# Front_2016.net
KiCad netlist of a schematic drawn in EAGLE
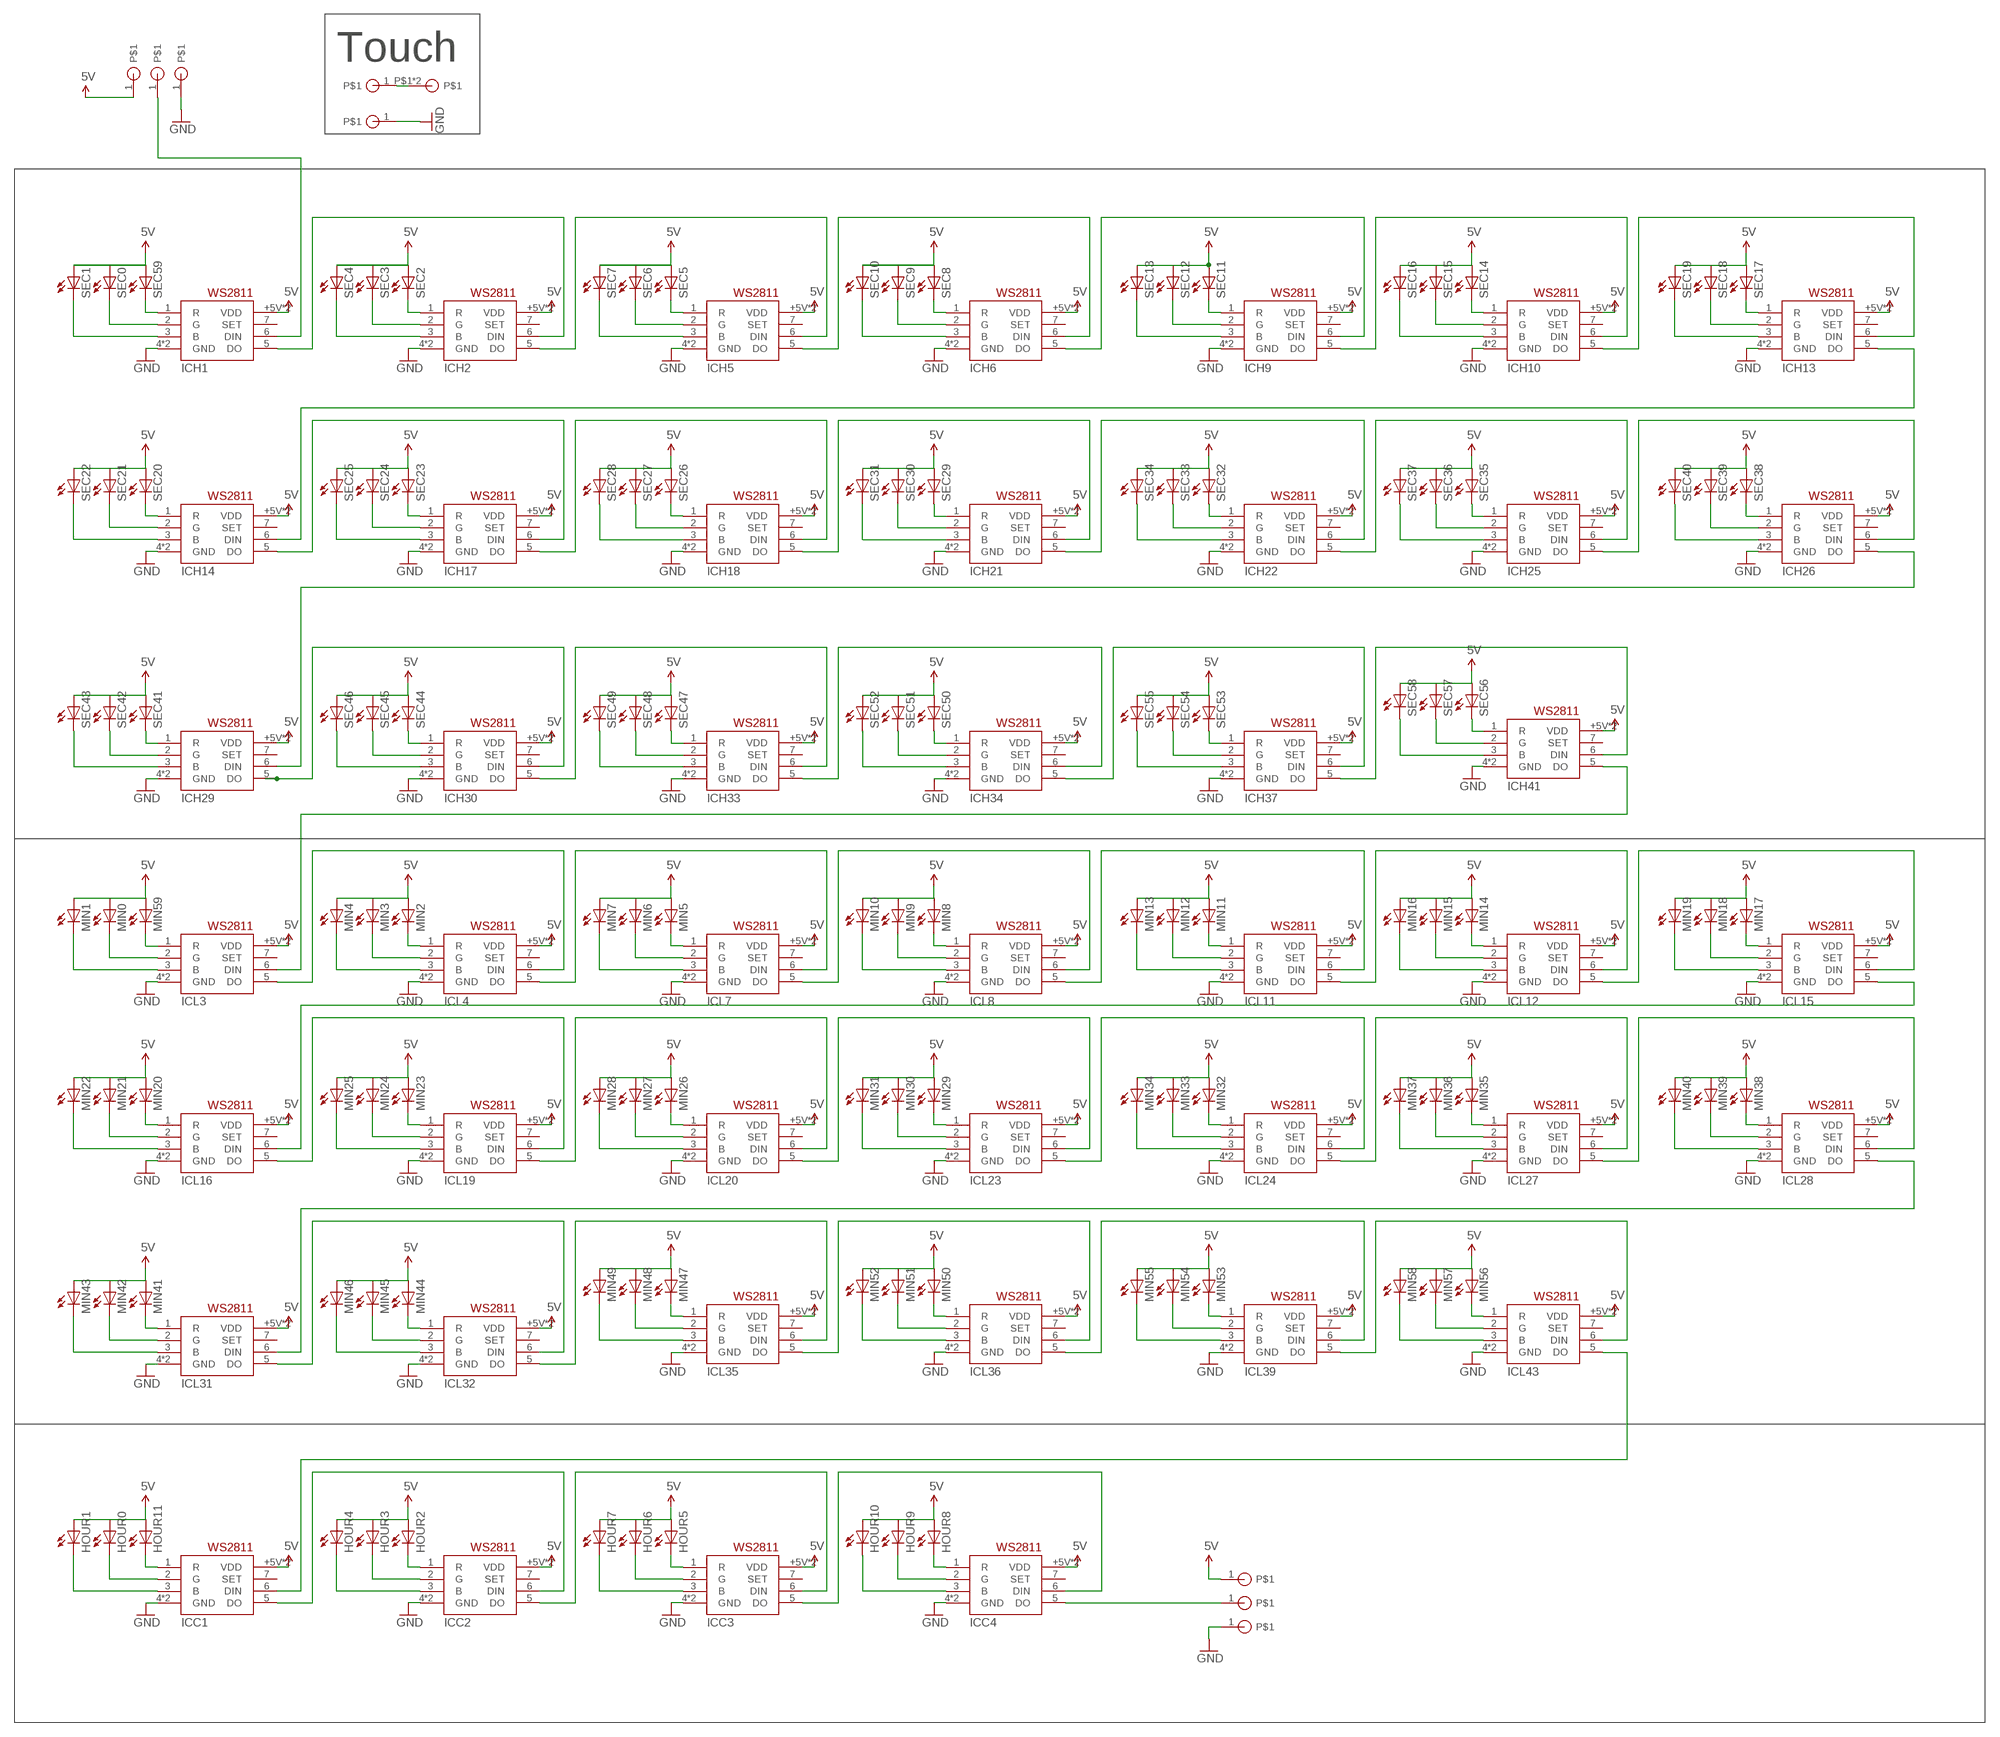
[diagram p0: schematic, sheet 1]

(export (version "E")
  (design (tool "Eeschema 10.0.6"))
  (components
    (comp (ref "+5V")
      (value "SOLDER_PAD")
      (footprint "eagle-import:SOLDER_PAD")
      (libsource (lib "eagle-import") (part "SOLDER_PAD"))
    )
    (comp (ref "+5V1")
      (value "SOLDER_PAD")
      (footprint "eagle-import:SOLDER_PAD")
      (libsource (lib "eagle-import") (part "SOLDER_PAD"))
    )
    (comp (ref "DIN")
      (value "SOLDER_PAD")
      (footprint "eagle-import:SOLDER_PAD")
      (libsource (lib "eagle-import") (part "SOLDER_PAD"))
    )
    (comp (ref "DOUT")
      (value "SOLDER_PAD")
      (footprint "eagle-import:SOLDER_PAD")
      (libsource (lib "eagle-import") (part "SOLDER_PAD"))
    )
    (comp (ref "GND")
      (value "SOLDER_PAD")
      (footprint "eagle-import:SOLDER_PAD")
      (libsource (lib "eagle-import") (part "SOLDER_PAD"))
    )
    (comp (ref "GND46")
      (value "SOLDER_PAD")
      (footprint "eagle-import:SOLDER_PAD")
      (libsource (lib "eagle-import") (part "SOLDER_PAD"))
    )
    (comp (ref "GND48")
      (value "SOLDER_PAD")
      (footprint "eagle-import:SOLDER_PAD")
      (libsource (lib "eagle-import") (part "SOLDER_PAD"))
    )
    (comp (ref "HOUR0")
      (value "LEDCHIPLED_0603")
      (footprint "eagle-import:CHIPLED_0603")
      (libsource (lib "eagle-import") (part "LEDCHIPLED_0603"))
    )
    (comp (ref "HOUR1")
      (value "LEDCHIPLED_0603")
      (footprint "eagle-import:CHIPLED_0603")
      (libsource (lib "eagle-import") (part "LEDCHIPLED_0603"))
    )
    (comp (ref "HOUR2")
      (value "LEDCHIPLED_0603")
      (footprint "eagle-import:CHIPLED_0603")
      (libsource (lib "eagle-import") (part "LEDCHIPLED_0603"))
    )
    (comp (ref "HOUR3")
      (value "LEDCHIPLED_0603")
      (footprint "eagle-import:CHIPLED_0603")
      (libsource (lib "eagle-import") (part "LEDCHIPLED_0603"))
    )
    (comp (ref "HOUR4")
      (value "LEDCHIPLED_0603")
      (footprint "eagle-import:CHIPLED_0603")
      (libsource (lib "eagle-import") (part "LEDCHIPLED_0603"))
    )
    (comp (ref "HOUR5")
      (value "LEDCHIPLED_0603")
      (footprint "eagle-import:CHIPLED_0603")
      (libsource (lib "eagle-import") (part "LEDCHIPLED_0603"))
    )
    (comp (ref "HOUR6")
      (value "LEDCHIPLED_0603")
      (footprint "eagle-import:CHIPLED_0603")
      (libsource (lib "eagle-import") (part "LEDCHIPLED_0603"))
    )
    (comp (ref "HOUR7")
      (value "LEDCHIPLED_0603")
      (footprint "eagle-import:CHIPLED_0603")
      (libsource (lib "eagle-import") (part "LEDCHIPLED_0603"))
    )
    (comp (ref "HOUR8")
      (value "LEDCHIPLED_0603")
      (footprint "eagle-import:CHIPLED_0603")
      (libsource (lib "eagle-import") (part "LEDCHIPLED_0603"))
    )
    (comp (ref "HOUR9")
      (value "LEDCHIPLED_0603")
      (footprint "eagle-import:CHIPLED_0603")
      (libsource (lib "eagle-import") (part "LEDCHIPLED_0603"))
    )
    (comp (ref "HOUR10")
      (value "LEDCHIPLED_0603")
      (footprint "eagle-import:CHIPLED_0603")
      (libsource (lib "eagle-import") (part "LEDCHIPLED_0603"))
    )
    (comp (ref "HOUR11")
      (value "LEDCHIPLED_0603")
      (footprint "eagle-import:CHIPLED_0603")
      (libsource (lib "eagle-import") (part "LEDCHIPLED_0603"))
    )
    (comp (ref "ICC1")
      (value "WS2811-SOP8")
      (footprint "eagle-import:SO08-SKINNYPADS")
      (libsource (lib "eagle-import") (part "WS2811-SOP8"))
    )
    (comp (ref "ICC2")
      (value "WS2811-SOP8")
      (footprint "eagle-import:SO08-SKINNYPADS")
      (libsource (lib "eagle-import") (part "WS2811-SOP8"))
    )
    (comp (ref "ICC3")
      (value "WS2811-SOP8")
      (footprint "eagle-import:SO08-SKINNYPADS")
      (libsource (lib "eagle-import") (part "WS2811-SOP8"))
    )
    (comp (ref "ICC4")
      (value "WS2811-SOP8")
      (footprint "eagle-import:SO08-SKINNYPADS")
      (libsource (lib "eagle-import") (part "WS2811-SOP8"))
    )
    (comp (ref "ICH1")
      (value "WS2811-SOP8")
      (footprint "eagle-import:SO08-SKINNYPADS")
      (libsource (lib "eagle-import") (part "WS2811-SOP8"))
    )
    (comp (ref "ICH2")
      (value "WS2811-SOP8")
      (footprint "eagle-import:SO08-SKINNYPADS")
      (libsource (lib "eagle-import") (part "WS2811-SOP8"))
    )
    (comp (ref "ICH5")
      (value "WS2811-SOP8")
      (footprint "eagle-import:SO08-SKINNYPADS")
      (libsource (lib "eagle-import") (part "WS2811-SOP8"))
    )
    (comp (ref "ICH6")
      (value "WS2811-SOP8")
      (footprint "eagle-import:SO08-SKINNYPADS")
      (libsource (lib "eagle-import") (part "WS2811-SOP8"))
    )
    (comp (ref "ICH9")
      (value "WS2811-SOP8")
      (footprint "eagle-import:SO08-SKINNYPADS")
      (libsource (lib "eagle-import") (part "WS2811-SOP8"))
    )
    (comp (ref "ICH10")
      (value "WS2811-SOP8")
      (footprint "eagle-import:SO08-SKINNYPADS")
      (libsource (lib "eagle-import") (part "WS2811-SOP8"))
    )
    (comp (ref "ICH13")
      (value "WS2811-SOP8")
      (footprint "eagle-import:SO08-SKINNYPADS")
      (libsource (lib "eagle-import") (part "WS2811-SOP8"))
    )
    (comp (ref "ICH14")
      (value "WS2811-SOP8")
      (footprint "eagle-import:SO08-SKINNYPADS")
      (libsource (lib "eagle-import") (part "WS2811-SOP8"))
    )
    (comp (ref "ICH17")
      (value "WS2811-SOP8")
      (footprint "eagle-import:SO08-SKINNYPADS")
      (libsource (lib "eagle-import") (part "WS2811-SOP8"))
    )
    (comp (ref "ICH18")
      (value "WS2811-SOP8")
      (footprint "eagle-import:SO08-SKINNYPADS")
      (libsource (lib "eagle-import") (part "WS2811-SOP8"))
    )
    (comp (ref "ICH21")
      (value "WS2811-SOP8")
      (footprint "eagle-import:SO08-SKINNYPADS")
      (libsource (lib "eagle-import") (part "WS2811-SOP8"))
    )
    (comp (ref "ICH22")
      (value "WS2811-SOP8")
      (footprint "eagle-import:SO08-SKINNYPADS")
      (libsource (lib "eagle-import") (part "WS2811-SOP8"))
    )
    (comp (ref "ICH25")
      (value "WS2811-SOP8")
      (footprint "eagle-import:SO08-SKINNYPADS")
      (libsource (lib "eagle-import") (part "WS2811-SOP8"))
    )
    (comp (ref "ICH26")
      (value "WS2811-SOP8")
      (footprint "eagle-import:SO08-SKINNYPADS")
      (libsource (lib "eagle-import") (part "WS2811-SOP8"))
    )
    (comp (ref "ICH29")
      (value "WS2811-SOP8")
      (footprint "eagle-import:SO08-SKINNYPADS")
      (libsource (lib "eagle-import") (part "WS2811-SOP8"))
    )
    (comp (ref "ICH30")
      (value "WS2811-SOP8")
      (footprint "eagle-import:SO08-SKINNYPADS")
      (libsource (lib "eagle-import") (part "WS2811-SOP8"))
    )
    (comp (ref "ICH33")
      (value "WS2811-SOP8")
      (footprint "eagle-import:SO08-SKINNYPADS")
      (libsource (lib "eagle-import") (part "WS2811-SOP8"))
    )
    (comp (ref "ICH34")
      (value "WS2811-SOP8")
      (footprint "eagle-import:SO08-SKINNYPADS")
      (libsource (lib "eagle-import") (part "WS2811-SOP8"))
    )
    (comp (ref "ICH37")
      (value "WS2811-SOP8")
      (footprint "eagle-import:SO08-SKINNYPADS")
      (libsource (lib "eagle-import") (part "WS2811-SOP8"))
    )
    (comp (ref "ICH41")
      (value "WS2811-SOP8")
      (footprint "eagle-import:SO08-SKINNYPADS")
      (libsource (lib "eagle-import") (part "WS2811-SOP8"))
    )
    (comp (ref "ICL3")
      (value "WS2811-SOP8")
      (footprint "eagle-import:SO08-SKINNYPADS")
      (libsource (lib "eagle-import") (part "WS2811-SOP8"))
    )
    (comp (ref "ICL4")
      (value "WS2811-SOP8")
      (footprint "eagle-import:SO08-SKINNYPADS")
      (libsource (lib "eagle-import") (part "WS2811-SOP8"))
    )
    (comp (ref "ICL7")
      (value "WS2811-SOP8")
      (footprint "eagle-import:SO08-SKINNYPADS")
      (libsource (lib "eagle-import") (part "WS2811-SOP8"))
    )
    (comp (ref "ICL8")
      (value "WS2811-SOP8")
      (footprint "eagle-import:SO08-SKINNYPADS")
      (libsource (lib "eagle-import") (part "WS2811-SOP8"))
    )
    (comp (ref "ICL11")
      (value "WS2811-SOP8")
      (footprint "eagle-import:SO08-SKINNYPADS")
      (libsource (lib "eagle-import") (part "WS2811-SOP8"))
    )
    (comp (ref "ICL12")
      (value "WS2811-SOP8")
      (footprint "eagle-import:SO08-SKINNYPADS")
      (libsource (lib "eagle-import") (part "WS2811-SOP8"))
    )
    (comp (ref "ICL15")
      (value "WS2811-SOP8")
      (footprint "eagle-import:SO08-SKINNYPADS")
      (libsource (lib "eagle-import") (part "WS2811-SOP8"))
    )
    (comp (ref "ICL16")
      (value "WS2811-SOP8")
      (footprint "eagle-import:SO08-SKINNYPADS")
      (libsource (lib "eagle-import") (part "WS2811-SOP8"))
    )
    (comp (ref "ICL19")
      (value "WS2811-SOP8")
      (footprint "eagle-import:SO08-SKINNYPADS")
      (libsource (lib "eagle-import") (part "WS2811-SOP8"))
    )
    (comp (ref "ICL20")
      (value "WS2811-SOP8")
      (footprint "eagle-import:SO08-SKINNYPADS")
      (libsource (lib "eagle-import") (part "WS2811-SOP8"))
    )
    (comp (ref "ICL23")
      (value "WS2811-SOP8")
      (footprint "eagle-import:SO08-SKINNYPADS")
      (libsource (lib "eagle-import") (part "WS2811-SOP8"))
    )
    (comp (ref "ICL24")
      (value "WS2811-SOP8")
      (footprint "eagle-import:SO08-SKINNYPADS")
      (libsource (lib "eagle-import") (part "WS2811-SOP8"))
    )
    (comp (ref "ICL27")
      (value "WS2811-SOP8")
      (footprint "eagle-import:SO08-SKINNYPADS")
      (libsource (lib "eagle-import") (part "WS2811-SOP8"))
    )
    (comp (ref "ICL28")
      (value "WS2811-SOP8")
      (footprint "eagle-import:SO08-SKINNYPADS")
      (libsource (lib "eagle-import") (part "WS2811-SOP8"))
    )
    (comp (ref "ICL31")
      (value "WS2811-SOP8")
      (footprint "eagle-import:SO08-SKINNYPADS")
      (libsource (lib "eagle-import") (part "WS2811-SOP8"))
    )
    (comp (ref "ICL32")
      (value "WS2811-SOP8")
      (footprint "eagle-import:SO08-SKINNYPADS")
      (libsource (lib "eagle-import") (part "WS2811-SOP8"))
    )
    (comp (ref "ICL35")
      (value "WS2811-SOP8")
      (footprint "eagle-import:SO08-SKINNYPADS")
      (libsource (lib "eagle-import") (part "WS2811-SOP8"))
    )
    (comp (ref "ICL36")
      (value "WS2811-SOP8")
      (footprint "eagle-import:SO08-SKINNYPADS")
      (libsource (lib "eagle-import") (part "WS2811-SOP8"))
    )
    (comp (ref "ICL39")
      (value "WS2811-SOP8")
      (footprint "eagle-import:SO08-SKINNYPADS")
      (libsource (lib "eagle-import") (part "WS2811-SOP8"))
    )
    (comp (ref "ICL43")
      (value "WS2811-SOP8")
      (footprint "eagle-import:SO08-SKINNYPADS")
      (libsource (lib "eagle-import") (part "WS2811-SOP8"))
    )
    (comp (ref "MIN0")
      (value "LEDCHIPLED_0603")
      (footprint "eagle-import:CHIPLED_0603")
      (libsource (lib "eagle-import") (part "LEDCHIPLED_0603"))
    )
    (comp (ref "MIN1")
      (value "LEDCHIPLED_0603")
      (footprint "eagle-import:CHIPLED_0603")
      (libsource (lib "eagle-import") (part "LEDCHIPLED_0603"))
    )
    (comp (ref "MIN2")
      (value "LEDCHIPLED_0603")
      (footprint "eagle-import:CHIPLED_0603")
      (libsource (lib "eagle-import") (part "LEDCHIPLED_0603"))
    )
    (comp (ref "MIN3")
      (value "LEDCHIPLED_0603")
      (footprint "eagle-import:CHIPLED_0603")
      (libsource (lib "eagle-import") (part "LEDCHIPLED_0603"))
    )
    (comp (ref "MIN4")
      (value "LEDCHIPLED_0603")
      (footprint "eagle-import:CHIPLED_0603")
      (libsource (lib "eagle-import") (part "LEDCHIPLED_0603"))
    )
    (comp (ref "MIN5")
      (value "LEDCHIPLED_0603")
      (footprint "eagle-import:CHIPLED_0603")
      (libsource (lib "eagle-import") (part "LEDCHIPLED_0603"))
    )
    (comp (ref "MIN6")
      (value "LEDCHIPLED_0603")
      (footprint "eagle-import:CHIPLED_0603")
      (libsource (lib "eagle-import") (part "LEDCHIPLED_0603"))
    )
    (comp (ref "MIN7")
      (value "LEDCHIPLED_0603")
      (footprint "eagle-import:CHIPLED_0603")
      (libsource (lib "eagle-import") (part "LEDCHIPLED_0603"))
    )
    (comp (ref "MIN8")
      (value "LEDCHIPLED_0603")
      (footprint "eagle-import:CHIPLED_0603")
      (libsource (lib "eagle-import") (part "LEDCHIPLED_0603"))
    )
    (comp (ref "MIN9")
      (value "LEDCHIPLED_0603")
      (footprint "eagle-import:CHIPLED_0603")
      (libsource (lib "eagle-import") (part "LEDCHIPLED_0603"))
    )
    (comp (ref "MIN10")
      (value "LEDCHIPLED_0603")
      (footprint "eagle-import:CHIPLED_0603")
      (libsource (lib "eagle-import") (part "LEDCHIPLED_0603"))
    )
    (comp (ref "MIN11")
      (value "LEDCHIPLED_0603")
      (footprint "eagle-import:CHIPLED_0603")
      (libsource (lib "eagle-import") (part "LEDCHIPLED_0603"))
    )
    (comp (ref "MIN12")
      (value "LEDCHIPLED_0603")
      (footprint "eagle-import:CHIPLED_0603")
      (libsource (lib "eagle-import") (part "LEDCHIPLED_0603"))
    )
    (comp (ref "MIN13")
      (value "LEDCHIPLED_0603")
      (footprint "eagle-import:CHIPLED_0603")
      (libsource (lib "eagle-import") (part "LEDCHIPLED_0603"))
    )
    (comp (ref "MIN14")
      (value "LEDCHIPLED_0603")
      (footprint "eagle-import:CHIPLED_0603")
      (libsource (lib "eagle-import") (part "LEDCHIPLED_0603"))
    )
    (comp (ref "MIN15")
      (value "LEDCHIPLED_0603")
      (footprint "eagle-import:CHIPLED_0603")
      (libsource (lib "eagle-import") (part "LEDCHIPLED_0603"))
    )
    (comp (ref "MIN16")
      (value "LEDCHIPLED_0603")
      (footprint "eagle-import:CHIPLED_0603")
      (libsource (lib "eagle-import") (part "LEDCHIPLED_0603"))
    )
    (comp (ref "MIN17")
      (value "LEDCHIPLED_0603")
      (footprint "eagle-import:CHIPLED_0603")
      (libsource (lib "eagle-import") (part "LEDCHIPLED_0603"))
    )
    (comp (ref "MIN18")
      (value "LEDCHIPLED_0603")
      (footprint "eagle-import:CHIPLED_0603")
      (libsource (lib "eagle-import") (part "LEDCHIPLED_0603"))
    )
    (comp (ref "MIN19")
      (value "LEDCHIPLED_0603")
      (footprint "eagle-import:CHIPLED_0603")
      (libsource (lib "eagle-import") (part "LEDCHIPLED_0603"))
    )
    (comp (ref "MIN20")
      (value "LEDCHIPLED_0603")
      (footprint "eagle-import:CHIPLED_0603")
      (libsource (lib "eagle-import") (part "LEDCHIPLED_0603"))
    )
    (comp (ref "MIN21")
      (value "LEDCHIPLED_0603")
      (footprint "eagle-import:CHIPLED_0603")
      (libsource (lib "eagle-import") (part "LEDCHIPLED_0603"))
    )
    (comp (ref "MIN22")
      (value "LEDCHIPLED_0603")
      (footprint "eagle-import:CHIPLED_0603")
      (libsource (lib "eagle-import") (part "LEDCHIPLED_0603"))
    )
    (comp (ref "MIN23")
      (value "LEDCHIPLED_0603")
      (footprint "eagle-import:CHIPLED_0603")
      (libsource (lib "eagle-import") (part "LEDCHIPLED_0603"))
    )
    (comp (ref "MIN24")
      (value "LEDCHIPLED_0603")
      (footprint "eagle-import:CHIPLED_0603")
      (libsource (lib "eagle-import") (part "LEDCHIPLED_0603"))
    )
    (comp (ref "MIN25")
      (value "LEDCHIPLED_0603")
      (footprint "eagle-import:CHIPLED_0603")
      (libsource (lib "eagle-import") (part "LEDCHIPLED_0603"))
    )
    (comp (ref "MIN26")
      (value "LEDCHIPLED_0603")
      (footprint "eagle-import:CHIPLED_0603")
      (libsource (lib "eagle-import") (part "LEDCHIPLED_0603"))
    )
    (comp (ref "MIN27")
      (value "LEDCHIPLED_0603")
      (footprint "eagle-import:CHIPLED_0603")
      (libsource (lib "eagle-import") (part "LEDCHIPLED_0603"))
    )
    (comp (ref "MIN28")
      (value "LEDCHIPLED_0603")
      (footprint "eagle-import:CHIPLED_0603")
      (libsource (lib "eagle-import") (part "LEDCHIPLED_0603"))
    )
    (comp (ref "MIN29")
      (value "LEDCHIPLED_0603")
      (footprint "eagle-import:CHIPLED_0603")
      (libsource (lib "eagle-import") (part "LEDCHIPLED_0603"))
    )
    (comp (ref "MIN30")
      (value "LEDCHIPLED_0603")
      (footprint "eagle-import:CHIPLED_0603")
      (libsource (lib "eagle-import") (part "LEDCHIPLED_0603"))
    )
    (comp (ref "MIN31")
      (value "LEDCHIPLED_0603")
      (footprint "eagle-import:CHIPLED_0603")
      (libsource (lib "eagle-import") (part "LEDCHIPLED_0603"))
    )
    (comp (ref "MIN32")
      (value "LEDCHIPLED_0603")
      (footprint "eagle-import:CHIPLED_0603")
      (libsource (lib "eagle-import") (part "LEDCHIPLED_0603"))
    )
    (comp (ref "MIN33")
      (value "LEDCHIPLED_0603")
      (footprint "eagle-import:CHIPLED_0603")
      (libsource (lib "eagle-import") (part "LEDCHIPLED_0603"))
    )
    (comp (ref "MIN34")
      (value "LEDCHIPLED_0603")
      (footprint "eagle-import:CHIPLED_0603")
      (libsource (lib "eagle-import") (part "LEDCHIPLED_0603"))
    )
    (comp (ref "MIN35")
      (value "LEDCHIPLED_0603")
      (footprint "eagle-import:CHIPLED_0603")
      (libsource (lib "eagle-import") (part "LEDCHIPLED_0603"))
    )
    (comp (ref "MIN36")
      (value "LEDCHIPLED_0603")
      (footprint "eagle-import:CHIPLED_0603")
      (libsource (lib "eagle-import") (part "LEDCHIPLED_0603"))
    )
    (comp (ref "MIN37")
      (value "LEDCHIPLED_0603")
      (footprint "eagle-import:CHIPLED_0603")
      (libsource (lib "eagle-import") (part "LEDCHIPLED_0603"))
    )
    (comp (ref "MIN38")
      (value "LEDCHIPLED_0603")
      (footprint "eagle-import:CHIPLED_0603")
      (libsource (lib "eagle-import") (part "LEDCHIPLED_0603"))
    )
    (comp (ref "MIN39")
      (value "LEDCHIPLED_0603")
      (footprint "eagle-import:CHIPLED_0603")
      (libsource (lib "eagle-import") (part "LEDCHIPLED_0603"))
    )
    (comp (ref "MIN40")
      (value "LEDCHIPLED_0603")
      (footprint "eagle-import:CHIPLED_0603")
      (libsource (lib "eagle-import") (part "LEDCHIPLED_0603"))
    )
    (comp (ref "MIN41")
      (value "LEDCHIPLED_0603")
      (footprint "eagle-import:CHIPLED_0603")
      (libsource (lib "eagle-import") (part "LEDCHIPLED_0603"))
    )
    (comp (ref "MIN42")
      (value "LEDCHIPLED_0603")
      (footprint "eagle-import:CHIPLED_0603")
      (libsource (lib "eagle-import") (part "LEDCHIPLED_0603"))
    )
    (comp (ref "MIN43")
      (value "LEDCHIPLED_0603")
      (footprint "eagle-import:CHIPLED_0603")
      (libsource (lib "eagle-import") (part "LEDCHIPLED_0603"))
    )
    (comp (ref "MIN44")
      (value "LEDCHIPLED_0603")
      (footprint "eagle-import:CHIPLED_0603")
      (libsource (lib "eagle-import") (part "LEDCHIPLED_0603"))
    )
    (comp (ref "MIN45")
      (value "LEDCHIPLED_0603")
      (footprint "eagle-import:CHIPLED_0603")
      (libsource (lib "eagle-import") (part "LEDCHIPLED_0603"))
    )
    (comp (ref "MIN46")
      (value "LEDCHIPLED_0603")
      (footprint "eagle-import:CHIPLED_0603")
      (libsource (lib "eagle-import") (part "LEDCHIPLED_0603"))
    )
    (comp (ref "MIN47")
      (value "LEDCHIPLED_0603")
      (footprint "eagle-import:CHIPLED_0603")
      (libsource (lib "eagle-import") (part "LEDCHIPLED_0603"))
    )
    (comp (ref "MIN48")
      (value "LEDCHIPLED_0603")
      (footprint "eagle-import:CHIPLED_0603")
      (libsource (lib "eagle-import") (part "LEDCHIPLED_0603"))
    )
    (comp (ref "MIN49")
      (value "LEDCHIPLED_0603")
      (footprint "eagle-import:CHIPLED_0603")
      (libsource (lib "eagle-import") (part "LEDCHIPLED_0603"))
    )
    (comp (ref "MIN50")
      (value "LEDCHIPLED_0603")
      (footprint "eagle-import:CHIPLED_0603")
      (libsource (lib "eagle-import") (part "LEDCHIPLED_0603"))
    )
    (comp (ref "MIN51")
      (value "LEDCHIPLED_0603")
      (footprint "eagle-import:CHIPLED_0603")
      (libsource (lib "eagle-import") (part "LEDCHIPLED_0603"))
    )
    (comp (ref "MIN52")
      (value "LEDCHIPLED_0603")
      (footprint "eagle-import:CHIPLED_0603")
      (libsource (lib "eagle-import") (part "LEDCHIPLED_0603"))
    )
    (comp (ref "MIN53")
      (value "LEDCHIPLED_0603")
      (footprint "eagle-import:CHIPLED_0603")
      (libsource (lib "eagle-import") (part "LEDCHIPLED_0603"))
    )
    (comp (ref "MIN54")
      (value "LEDCHIPLED_0603")
      (footprint "eagle-import:CHIPLED_0603")
      (libsource (lib "eagle-import") (part "LEDCHIPLED_0603"))
    )
    (comp (ref "MIN55")
      (value "LEDCHIPLED_0603")
      (footprint "eagle-import:CHIPLED_0603")
      (libsource (lib "eagle-import") (part "LEDCHIPLED_0603"))
    )
    (comp (ref "MIN56")
      (value "LEDCHIPLED_0603")
      (footprint "eagle-import:CHIPLED_0603")
      (libsource (lib "eagle-import") (part "LEDCHIPLED_0603"))
    )
    (comp (ref "MIN57")
      (value "LEDCHIPLED_0603")
      (footprint "eagle-import:CHIPLED_0603")
      (libsource (lib "eagle-import") (part "LEDCHIPLED_0603"))
    )
    (comp (ref "MIN58")
      (value "LEDCHIPLED_0603")
      (footprint "eagle-import:CHIPLED_0603")
      (libsource (lib "eagle-import") (part "LEDCHIPLED_0603"))
    )
    (comp (ref "MIN59")
      (value "LEDCHIPLED_0603")
      (footprint "eagle-import:CHIPLED_0603")
      (libsource (lib "eagle-import") (part "LEDCHIPLED_0603"))
    )
    (comp (ref "SEC0")
      (value "LEDCHIPLED_0603")
      (footprint "eagle-import:CHIPLED_0603")
      (libsource (lib "eagle-import") (part "LEDCHIPLED_0603"))
    )
    (comp (ref "SEC1")
      (value "LEDCHIPLED_0603")
      (footprint "eagle-import:CHIPLED_0603")
      (libsource (lib "eagle-import") (part "LEDCHIPLED_0603"))
    )
    (comp (ref "SEC2")
      (value "LEDCHIPLED_0603")
      (footprint "eagle-import:CHIPLED_0603")
      (libsource (lib "eagle-import") (part "LEDCHIPLED_0603"))
    )
    (comp (ref "SEC3")
      (value "LEDCHIPLED_0603")
      (footprint "eagle-import:CHIPLED_0603")
      (libsource (lib "eagle-import") (part "LEDCHIPLED_0603"))
    )
    (comp (ref "SEC4")
      (value "LEDCHIPLED_0603")
      (footprint "eagle-import:CHIPLED_0603")
      (libsource (lib "eagle-import") (part "LEDCHIPLED_0603"))
    )
    (comp (ref "SEC5")
      (value "LEDCHIPLED_0603")
      (footprint "eagle-import:CHIPLED_0603")
      (libsource (lib "eagle-import") (part "LEDCHIPLED_0603"))
    )
    (comp (ref "SEC6")
      (value "LEDCHIPLED_0603")
      (footprint "eagle-import:CHIPLED_0603")
      (libsource (lib "eagle-import") (part "LEDCHIPLED_0603"))
    )
    (comp (ref "SEC7")
      (value "LEDCHIPLED_0603")
      (footprint "eagle-import:CHIPLED_0603")
      (libsource (lib "eagle-import") (part "LEDCHIPLED_0603"))
    )
    (comp (ref "SEC8")
      (value "LEDCHIPLED_0603")
      (footprint "eagle-import:CHIPLED_0603")
      (libsource (lib "eagle-import") (part "LEDCHIPLED_0603"))
    )
    (comp (ref "SEC9")
      (value "LEDCHIPLED_0603")
      (footprint "eagle-import:CHIPLED_0603")
      (libsource (lib "eagle-import") (part "LEDCHIPLED_0603"))
    )
    (comp (ref "SEC10")
      (value "LEDCHIPLED_0603")
      (footprint "eagle-import:CHIPLED_0603")
      (libsource (lib "eagle-import") (part "LEDCHIPLED_0603"))
    )
    (comp (ref "SEC11")
      (value "LEDCHIPLED_0603")
      (footprint "eagle-import:CHIPLED_0603")
      (libsource (lib "eagle-import") (part "LEDCHIPLED_0603"))
    )
    (comp (ref "SEC12")
      (value "LEDCHIPLED_0603")
      (footprint "eagle-import:CHIPLED_0603")
      (libsource (lib "eagle-import") (part "LEDCHIPLED_0603"))
    )
    (comp (ref "SEC13")
      (value "LEDCHIPLED_0603")
      (footprint "eagle-import:CHIPLED_0603")
      (libsource (lib "eagle-import") (part "LEDCHIPLED_0603"))
    )
    (comp (ref "SEC14")
      (value "LEDCHIPLED_0603")
      (footprint "eagle-import:CHIPLED_0603")
      (libsource (lib "eagle-import") (part "LEDCHIPLED_0603"))
    )
    (comp (ref "SEC15")
      (value "LEDCHIPLED_0603")
      (footprint "eagle-import:CHIPLED_0603")
      (libsource (lib "eagle-import") (part "LEDCHIPLED_0603"))
    )
    (comp (ref "SEC16")
      (value "LEDCHIPLED_0603")
      (footprint "eagle-import:CHIPLED_0603")
      (libsource (lib "eagle-import") (part "LEDCHIPLED_0603"))
    )
    (comp (ref "SEC17")
      (value "LEDCHIPLED_0603")
      (footprint "eagle-import:CHIPLED_0603")
      (libsource (lib "eagle-import") (part "LEDCHIPLED_0603"))
    )
    (comp (ref "SEC18")
      (value "LEDCHIPLED_0603")
      (footprint "eagle-import:CHIPLED_0603")
      (libsource (lib "eagle-import") (part "LEDCHIPLED_0603"))
    )
    (comp (ref "SEC19")
      (value "LEDCHIPLED_0603")
      (footprint "eagle-import:CHIPLED_0603")
      (libsource (lib "eagle-import") (part "LEDCHIPLED_0603"))
    )
    (comp (ref "SEC20")
      (value "LEDCHIPLED_0603")
      (footprint "eagle-import:CHIPLED_0603")
      (libsource (lib "eagle-import") (part "LEDCHIPLED_0603"))
    )
    (comp (ref "SEC21")
      (value "LEDCHIPLED_0603")
      (footprint "eagle-import:CHIPLED_0603")
      (libsource (lib "eagle-import") (part "LEDCHIPLED_0603"))
    )
    (comp (ref "SEC22")
      (value "LEDCHIPLED_0603")
      (footprint "eagle-import:CHIPLED_0603")
      (libsource (lib "eagle-import") (part "LEDCHIPLED_0603"))
    )
    (comp (ref "SEC23")
      (value "LEDCHIPLED_0603")
      (footprint "eagle-import:CHIPLED_0603")
      (libsource (lib "eagle-import") (part "LEDCHIPLED_0603"))
    )
    (comp (ref "SEC24")
      (value "LEDCHIPLED_0603")
      (footprint "eagle-import:CHIPLED_0603")
      (libsource (lib "eagle-import") (part "LEDCHIPLED_0603"))
    )
    (comp (ref "SEC25")
      (value "LEDCHIPLED_0603")
      (footprint "eagle-import:CHIPLED_0603")
      (libsource (lib "eagle-import") (part "LEDCHIPLED_0603"))
    )
    (comp (ref "SEC26")
      (value "LEDCHIPLED_0603")
      (footprint "eagle-import:CHIPLED_0603")
      (libsource (lib "eagle-import") (part "LEDCHIPLED_0603"))
    )
    (comp (ref "SEC27")
      (value "LEDCHIPLED_0603")
      (footprint "eagle-import:CHIPLED_0603")
      (libsource (lib "eagle-import") (part "LEDCHIPLED_0603"))
    )
    (comp (ref "SEC28")
      (value "LEDCHIPLED_0603")
      (footprint "eagle-import:CHIPLED_0603")
      (libsource (lib "eagle-import") (part "LEDCHIPLED_0603"))
    )
    (comp (ref "SEC29")
      (value "LEDCHIPLED_0603")
      (footprint "eagle-import:CHIPLED_0603")
      (libsource (lib "eagle-import") (part "LEDCHIPLED_0603"))
    )
    (comp (ref "SEC30")
      (value "LEDCHIPLED_0603")
      (footprint "eagle-import:CHIPLED_0603")
      (libsource (lib "eagle-import") (part "LEDCHIPLED_0603"))
    )
    (comp (ref "SEC31")
      (value "LEDCHIPLED_0603")
      (footprint "eagle-import:CHIPLED_0603")
      (libsource (lib "eagle-import") (part "LEDCHIPLED_0603"))
    )
    (comp (ref "SEC32")
      (value "LEDCHIPLED_0603")
      (footprint "eagle-import:CHIPLED_0603")
      (libsource (lib "eagle-import") (part "LEDCHIPLED_0603"))
    )
    (comp (ref "SEC33")
      (value "LEDCHIPLED_0603")
      (footprint "eagle-import:CHIPLED_0603")
      (libsource (lib "eagle-import") (part "LEDCHIPLED_0603"))
    )
    (comp (ref "SEC34")
      (value "LEDCHIPLED_0603")
      (footprint "eagle-import:CHIPLED_0603")
      (libsource (lib "eagle-import") (part "LEDCHIPLED_0603"))
    )
    (comp (ref "SEC35")
      (value "LEDCHIPLED_0603")
      (footprint "eagle-import:CHIPLED_0603")
      (libsource (lib "eagle-import") (part "LEDCHIPLED_0603"))
    )
    (comp (ref "SEC36")
      (value "LEDCHIPLED_0603")
      (footprint "eagle-import:CHIPLED_0603")
      (libsource (lib "eagle-import") (part "LEDCHIPLED_0603"))
    )
    (comp (ref "SEC37")
      (value "LEDCHIPLED_0603")
      (footprint "eagle-import:CHIPLED_0603")
      (libsource (lib "eagle-import") (part "LEDCHIPLED_0603"))
    )
    (comp (ref "SEC38")
      (value "LEDCHIPLED_0603")
      (footprint "eagle-import:CHIPLED_0603")
      (libsource (lib "eagle-import") (part "LEDCHIPLED_0603"))
    )
    (comp (ref "SEC39")
      (value "LEDCHIPLED_0603")
      (footprint "eagle-import:CHIPLED_0603")
      (libsource (lib "eagle-import") (part "LEDCHIPLED_0603"))
    )
    (comp (ref "SEC40")
      (value "LEDCHIPLED_0603")
      (footprint "eagle-import:CHIPLED_0603")
      (libsource (lib "eagle-import") (part "LEDCHIPLED_0603"))
    )
    (comp (ref "SEC41")
      (value "LEDCHIPLED_0603")
      (footprint "eagle-import:CHIPLED_0603")
      (libsource (lib "eagle-import") (part "LEDCHIPLED_0603"))
    )
    (comp (ref "SEC42")
      (value "LEDCHIPLED_0603")
      (footprint "eagle-import:CHIPLED_0603")
      (libsource (lib "eagle-import") (part "LEDCHIPLED_0603"))
    )
    (comp (ref "SEC43")
      (value "LEDCHIPLED_0603")
      (footprint "eagle-import:CHIPLED_0603")
      (libsource (lib "eagle-import") (part "LEDCHIPLED_0603"))
    )
    (comp (ref "SEC44")
      (value "LEDCHIPLED_0603")
      (footprint "eagle-import:CHIPLED_0603")
      (libsource (lib "eagle-import") (part "LEDCHIPLED_0603"))
    )
    (comp (ref "SEC45")
      (value "LEDCHIPLED_0603")
      (footprint "eagle-import:CHIPLED_0603")
      (libsource (lib "eagle-import") (part "LEDCHIPLED_0603"))
    )
    (comp (ref "SEC46")
      (value "LEDCHIPLED_0603")
      (footprint "eagle-import:CHIPLED_0603")
      (libsource (lib "eagle-import") (part "LEDCHIPLED_0603"))
    )
    (comp (ref "SEC47")
      (value "LEDCHIPLED_0603")
      (footprint "eagle-import:CHIPLED_0603")
      (libsource (lib "eagle-import") (part "LEDCHIPLED_0603"))
    )
    (comp (ref "SEC48")
      (value "LEDCHIPLED_0603")
      (footprint "eagle-import:CHIPLED_0603")
      (libsource (lib "eagle-import") (part "LEDCHIPLED_0603"))
    )
    (comp (ref "SEC49")
      (value "LEDCHIPLED_0603")
      (footprint "eagle-import:CHIPLED_0603")
      (libsource (lib "eagle-import") (part "LEDCHIPLED_0603"))
    )
    (comp (ref "SEC50")
      (value "LEDCHIPLED_0603")
      (footprint "eagle-import:CHIPLED_0603")
      (libsource (lib "eagle-import") (part "LEDCHIPLED_0603"))
    )
    (comp (ref "SEC51")
      (value "LEDCHIPLED_0603")
      (footprint "eagle-import:CHIPLED_0603")
      (libsource (lib "eagle-import") (part "LEDCHIPLED_0603"))
    )
    (comp (ref "SEC52")
      (value "LEDCHIPLED_0603")
      (footprint "eagle-import:CHIPLED_0603")
      (libsource (lib "eagle-import") (part "LEDCHIPLED_0603"))
    )
    (comp (ref "SEC53")
      (value "LEDCHIPLED_0603")
      (footprint "eagle-import:CHIPLED_0603")
      (libsource (lib "eagle-import") (part "LEDCHIPLED_0603"))
    )
    (comp (ref "SEC54")
      (value "LEDCHIPLED_0603")
      (footprint "eagle-import:CHIPLED_0603")
      (libsource (lib "eagle-import") (part "LEDCHIPLED_0603"))
    )
    (comp (ref "SEC55")
      (value "LEDCHIPLED_0603")
      (footprint "eagle-import:CHIPLED_0603")
      (libsource (lib "eagle-import") (part "LEDCHIPLED_0603"))
    )
    (comp (ref "SEC56")
      (value "LEDCHIPLED_0603")
      (footprint "eagle-import:CHIPLED_0603")
      (libsource (lib "eagle-import") (part "LEDCHIPLED_0603"))
    )
    (comp (ref "SEC57")
      (value "LEDCHIPLED_0603")
      (footprint "eagle-import:CHIPLED_0603")
      (libsource (lib "eagle-import") (part "LEDCHIPLED_0603"))
    )
    (comp (ref "SEC58")
      (value "LEDCHIPLED_0603")
      (footprint "eagle-import:CHIPLED_0603")
      (libsource (lib "eagle-import") (part "LEDCHIPLED_0603"))
    )
    (comp (ref "SEC59")
      (value "LEDCHIPLED_0603")
      (footprint "eagle-import:CHIPLED_0603")
      (libsource (lib "eagle-import") (part "LEDCHIPLED_0603"))
    )
    (comp (ref "TOUCH")
      (value "SOLDER_PAD")
      (footprint "eagle-import:SOLDER_PAD")
      (libsource (lib "eagle-import") (part "SOLDER_PAD"))
    )
    (comp (ref "U$2")
      (value "TOUCH_PAD_LARGE")
      (footprint "eagle-import:TOUCH_PAD_LARGE")
      (libsource (lib "eagle-import") (part "TOUCH_PAD_LARGE"))
    )
  )
  (nets
    (net (code "1") (name "5V") (class "Default")
      (node (ref "+5V") (pin "1") (pinfunction "P$1_1") (pintype "bidirectional"))
      (node (ref "+5V1") (pin "1") (pinfunction "P$1_1") (pintype "bidirectional"))
      (node (ref "HOUR0") (pin "A") (pinfunction "A_A") (pintype "passive"))
      (node (ref "HOUR1") (pin "A") (pinfunction "A_A") (pintype "passive"))
      (node (ref "HOUR10") (pin "A") (pinfunction "A_A") (pintype "passive"))
      (node (ref "HOUR11") (pin "A") (pinfunction "A_A") (pintype "passive"))
      (node (ref "HOUR2") (pin "A") (pinfunction "A_A") (pintype "passive"))
      (node (ref "HOUR3") (pin "A") (pinfunction "A_A") (pintype "passive"))
      (node (ref "HOUR4") (pin "A") (pinfunction "A_A") (pintype "passive"))
      (node (ref "HOUR5") (pin "A") (pinfunction "A_A") (pintype "passive"))
      (node (ref "HOUR6") (pin "A") (pinfunction "A_A") (pintype "passive"))
      (node (ref "HOUR7") (pin "A") (pinfunction "A_A") (pintype "passive"))
      (node (ref "HOUR8") (pin "A") (pinfunction "A_A") (pintype "passive"))
      (node (ref "HOUR9") (pin "A") (pinfunction "A_A") (pintype "passive"))
      (node (ref "ICC1") (pin "+5V") (pinfunction "VDD_+5V") (pintype "power_in"))
      (node (ref "ICC1") (pin "8") (pinfunction "VDD_8") (pintype "power_in"))
      (node (ref "ICC2") (pin "+5V") (pinfunction "VDD_+5V") (pintype "power_in"))
      (node (ref "ICC2") (pin "8") (pinfunction "VDD_8") (pintype "power_in"))
      (node (ref "ICC3") (pin "+5V") (pinfunction "VDD_+5V") (pintype "power_in"))
      (node (ref "ICC3") (pin "8") (pinfunction "VDD_8") (pintype "power_in"))
      (node (ref "ICC4") (pin "+5V") (pinfunction "VDD_+5V") (pintype "power_in"))
      (node (ref "ICC4") (pin "8") (pinfunction "VDD_8") (pintype "power_in"))
      (node (ref "ICH1") (pin "+5V") (pinfunction "VDD_+5V") (pintype "power_in"))
      (node (ref "ICH1") (pin "8") (pinfunction "VDD_8") (pintype "power_in"))
      (node (ref "ICH10") (pin "+5V") (pinfunction "VDD_+5V") (pintype "power_in"))
      (node (ref "ICH10") (pin "8") (pinfunction "VDD_8") (pintype "power_in"))
      (node (ref "ICH13") (pin "+5V") (pinfunction "VDD_+5V") (pintype "power_in"))
      (node (ref "ICH13") (pin "8") (pinfunction "VDD_8") (pintype "power_in"))
      (node (ref "ICH14") (pin "+5V") (pinfunction "VDD_+5V") (pintype "power_in"))
      (node (ref "ICH14") (pin "8") (pinfunction "VDD_8") (pintype "power_in"))
      (node (ref "ICH17") (pin "+5V") (pinfunction "VDD_+5V") (pintype "power_in"))
      (node (ref "ICH17") (pin "8") (pinfunction "VDD_8") (pintype "power_in"))
      (node (ref "ICH18") (pin "+5V") (pinfunction "VDD_+5V") (pintype "power_in"))
      (node (ref "ICH18") (pin "8") (pinfunction "VDD_8") (pintype "power_in"))
      (node (ref "ICH2") (pin "+5V") (pinfunction "VDD_+5V") (pintype "power_in"))
      (node (ref "ICH2") (pin "8") (pinfunction "VDD_8") (pintype "power_in"))
      (node (ref "ICH21") (pin "+5V") (pinfunction "VDD_+5V") (pintype "power_in"))
      (node (ref "ICH21") (pin "8") (pinfunction "VDD_8") (pintype "power_in"))
      (node (ref "ICH22") (pin "+5V") (pinfunction "VDD_+5V") (pintype "power_in"))
      (node (ref "ICH22") (pin "8") (pinfunction "VDD_8") (pintype "power_in"))
      (node (ref "ICH25") (pin "+5V") (pinfunction "VDD_+5V") (pintype "power_in"))
      (node (ref "ICH25") (pin "8") (pinfunction "VDD_8") (pintype "power_in"))
      (node (ref "ICH26") (pin "+5V") (pinfunction "VDD_+5V") (pintype "power_in"))
      (node (ref "ICH26") (pin "8") (pinfunction "VDD_8") (pintype "power_in"))
      (node (ref "ICH29") (pin "+5V") (pinfunction "VDD_+5V") (pintype "power_in"))
      (node (ref "ICH29") (pin "8") (pinfunction "VDD_8") (pintype "power_in"))
      (node (ref "ICH30") (pin "+5V") (pinfunction "VDD_+5V") (pintype "power_in"))
      (node (ref "ICH30") (pin "8") (pinfunction "VDD_8") (pintype "power_in"))
      (node (ref "ICH33") (pin "+5V") (pinfunction "VDD_+5V") (pintype "power_in"))
      (node (ref "ICH33") (pin "8") (pinfunction "VDD_8") (pintype "power_in"))
      (node (ref "ICH34") (pin "+5V") (pinfunction "VDD_+5V") (pintype "power_in"))
      (node (ref "ICH34") (pin "8") (pinfunction "VDD_8") (pintype "power_in"))
      (node (ref "ICH37") (pin "+5V") (pinfunction "VDD_+5V") (pintype "power_in"))
      (node (ref "ICH37") (pin "8") (pinfunction "VDD_8") (pintype "power_in"))
      (node (ref "ICH41") (pin "+5V") (pinfunction "VDD_+5V") (pintype "power_in"))
      (node (ref "ICH41") (pin "8") (pinfunction "VDD_8") (pintype "power_in"))
      (node (ref "ICH5") (pin "+5V") (pinfunction "VDD_+5V") (pintype "power_in"))
      (node (ref "ICH5") (pin "8") (pinfunction "VDD_8") (pintype "power_in"))
      (node (ref "ICH6") (pin "+5V") (pinfunction "VDD_+5V") (pintype "power_in"))
      (node (ref "ICH6") (pin "8") (pinfunction "VDD_8") (pintype "power_in"))
      (node (ref "ICH9") (pin "+5V") (pinfunction "VDD_+5V") (pintype "power_in"))
      (node (ref "ICH9") (pin "8") (pinfunction "VDD_8") (pintype "power_in"))
      (node (ref "ICL11") (pin "+5V") (pinfunction "VDD_+5V") (pintype "power_in"))
      (node (ref "ICL11") (pin "8") (pinfunction "VDD_8") (pintype "power_in"))
      (node (ref "ICL12") (pin "+5V") (pinfunction "VDD_+5V") (pintype "power_in"))
      (node (ref "ICL12") (pin "8") (pinfunction "VDD_8") (pintype "power_in"))
      (node (ref "ICL15") (pin "+5V") (pinfunction "VDD_+5V") (pintype "power_in"))
      (node (ref "ICL15") (pin "8") (pinfunction "VDD_8") (pintype "power_in"))
      (node (ref "ICL16") (pin "+5V") (pinfunction "VDD_+5V") (pintype "power_in"))
      (node (ref "ICL16") (pin "8") (pinfunction "VDD_8") (pintype "power_in"))
      (node (ref "ICL19") (pin "+5V") (pinfunction "VDD_+5V") (pintype "power_in"))
      (node (ref "ICL19") (pin "8") (pinfunction "VDD_8") (pintype "power_in"))
      (node (ref "ICL20") (pin "+5V") (pinfunction "VDD_+5V") (pintype "power_in"))
      (node (ref "ICL20") (pin "8") (pinfunction "VDD_8") (pintype "power_in"))
      (node (ref "ICL23") (pin "+5V") (pinfunction "VDD_+5V") (pintype "power_in"))
      (node (ref "ICL23") (pin "8") (pinfunction "VDD_8") (pintype "power_in"))
      (node (ref "ICL24") (pin "+5V") (pinfunction "VDD_+5V") (pintype "power_in"))
      (node (ref "ICL24") (pin "8") (pinfunction "VDD_8") (pintype "power_in"))
      (node (ref "ICL27") (pin "+5V") (pinfunction "VDD_+5V") (pintype "power_in"))
      (node (ref "ICL27") (pin "8") (pinfunction "VDD_8") (pintype "power_in"))
      (node (ref "ICL28") (pin "+5V") (pinfunction "VDD_+5V") (pintype "power_in"))
      (node (ref "ICL28") (pin "8") (pinfunction "VDD_8") (pintype "power_in"))
      (node (ref "ICL3") (pin "+5V") (pinfunction "VDD_+5V") (pintype "power_in"))
      (node (ref "ICL3") (pin "8") (pinfunction "VDD_8") (pintype "power_in"))
      (node (ref "ICL31") (pin "+5V") (pinfunction "VDD_+5V") (pintype "power_in"))
      (node (ref "ICL31") (pin "8") (pinfunction "VDD_8") (pintype "power_in"))
      (node (ref "ICL32") (pin "+5V") (pinfunction "VDD_+5V") (pintype "power_in"))
      (node (ref "ICL32") (pin "8") (pinfunction "VDD_8") (pintype "power_in"))
      (node (ref "ICL35") (pin "+5V") (pinfunction "VDD_+5V") (pintype "power_in"))
      (node (ref "ICL35") (pin "8") (pinfunction "VDD_8") (pintype "power_in"))
      (node (ref "ICL36") (pin "+5V") (pinfunction "VDD_+5V") (pintype "power_in"))
      (node (ref "ICL36") (pin "8") (pinfunction "VDD_8") (pintype "power_in"))
      (node (ref "ICL39") (pin "+5V") (pinfunction "VDD_+5V") (pintype "power_in"))
      (node (ref "ICL39") (pin "8") (pinfunction "VDD_8") (pintype "power_in"))
      (node (ref "ICL4") (pin "+5V") (pinfunction "VDD_+5V") (pintype "power_in"))
      (node (ref "ICL4") (pin "8") (pinfunction "VDD_8") (pintype "power_in"))
      (node (ref "ICL43") (pin "+5V") (pinfunction "VDD_+5V") (pintype "power_in"))
      (node (ref "ICL43") (pin "8") (pinfunction "VDD_8") (pintype "power_in"))
      (node (ref "ICL7") (pin "+5V") (pinfunction "VDD_+5V") (pintype "power_in"))
      (node (ref "ICL7") (pin "8") (pinfunction "VDD_8") (pintype "power_in"))
      (node (ref "ICL8") (pin "+5V") (pinfunction "VDD_+5V") (pintype "power_in"))
      (node (ref "ICL8") (pin "8") (pinfunction "VDD_8") (pintype "power_in"))
      (node (ref "MIN0") (pin "A") (pinfunction "A_A") (pintype "passive"))
      (node (ref "MIN1") (pin "A") (pinfunction "A_A") (pintype "passive"))
      (node (ref "MIN10") (pin "A") (pinfunction "A_A") (pintype "passive"))
      (node (ref "MIN11") (pin "A") (pinfunction "A_A") (pintype "passive"))
      (node (ref "MIN12") (pin "A") (pinfunction "A_A") (pintype "passive"))
      (node (ref "MIN13") (pin "A") (pinfunction "A_A") (pintype "passive"))
      (node (ref "MIN14") (pin "A") (pinfunction "A_A") (pintype "passive"))
      (node (ref "MIN15") (pin "A") (pinfunction "A_A") (pintype "passive"))
      (node (ref "MIN16") (pin "A") (pinfunction "A_A") (pintype "passive"))
      (node (ref "MIN17") (pin "A") (pinfunction "A_A") (pintype "passive"))
      (node (ref "MIN18") (pin "A") (pinfunction "A_A") (pintype "passive"))
      (node (ref "MIN19") (pin "A") (pinfunction "A_A") (pintype "passive"))
      (node (ref "MIN2") (pin "A") (pinfunction "A_A") (pintype "passive"))
      (node (ref "MIN20") (pin "A") (pinfunction "A_A") (pintype "passive"))
      (node (ref "MIN21") (pin "A") (pinfunction "A_A") (pintype "passive"))
      (node (ref "MIN22") (pin "A") (pinfunction "A_A") (pintype "passive"))
      (node (ref "MIN23") (pin "A") (pinfunction "A_A") (pintype "passive"))
      (node (ref "MIN24") (pin "A") (pinfunction "A_A") (pintype "passive"))
      (node (ref "MIN25") (pin "A") (pinfunction "A_A") (pintype "passive"))
      (node (ref "MIN26") (pin "A") (pinfunction "A_A") (pintype "passive"))
      (node (ref "MIN27") (pin "A") (pinfunction "A_A") (pintype "passive"))
      (node (ref "MIN28") (pin "A") (pinfunction "A_A") (pintype "passive"))
      (node (ref "MIN29") (pin "A") (pinfunction "A_A") (pintype "passive"))
      (node (ref "MIN3") (pin "A") (pinfunction "A_A") (pintype "passive"))
      (node (ref "MIN30") (pin "A") (pinfunction "A_A") (pintype "passive"))
      (node (ref "MIN31") (pin "A") (pinfunction "A_A") (pintype "passive"))
      (node (ref "MIN32") (pin "A") (pinfunction "A_A") (pintype "passive"))
      (node (ref "MIN33") (pin "A") (pinfunction "A_A") (pintype "passive"))
      (node (ref "MIN34") (pin "A") (pinfunction "A_A") (pintype "passive"))
      (node (ref "MIN35") (pin "A") (pinfunction "A_A") (pintype "passive"))
      (node (ref "MIN36") (pin "A") (pinfunction "A_A") (pintype "passive"))
      (node (ref "MIN37") (pin "A") (pinfunction "A_A") (pintype "passive"))
      (node (ref "MIN38") (pin "A") (pinfunction "A_A") (pintype "passive"))
      (node (ref "MIN39") (pin "A") (pinfunction "A_A") (pintype "passive"))
      (node (ref "MIN4") (pin "A") (pinfunction "A_A") (pintype "passive"))
      (node (ref "MIN40") (pin "A") (pinfunction "A_A") (pintype "passive"))
      (node (ref "MIN41") (pin "A") (pinfunction "A_A") (pintype "passive"))
      (node (ref "MIN42") (pin "A") (pinfunction "A_A") (pintype "passive"))
      (node (ref "MIN43") (pin "A") (pinfunction "A_A") (pintype "passive"))
      (node (ref "MIN44") (pin "A") (pinfunction "A_A") (pintype "passive"))
      (node (ref "MIN45") (pin "A") (pinfunction "A_A") (pintype "passive"))
      (node (ref "MIN46") (pin "A") (pinfunction "A_A") (pintype "passive"))
      (node (ref "MIN47") (pin "A") (pinfunction "A_A") (pintype "passive"))
      (node (ref "MIN48") (pin "A") (pinfunction "A_A") (pintype "passive"))
      (node (ref "MIN49") (pin "A") (pinfunction "A_A") (pintype "passive"))
      (node (ref "MIN5") (pin "A") (pinfunction "A_A") (pintype "passive"))
      (node (ref "MIN50") (pin "A") (pinfunction "A_A") (pintype "passive"))
      (node (ref "MIN51") (pin "A") (pinfunction "A_A") (pintype "passive"))
      (node (ref "MIN52") (pin "A") (pinfunction "A_A") (pintype "passive"))
      (node (ref "MIN53") (pin "A") (pinfunction "A_A") (pintype "passive"))
      (node (ref "MIN54") (pin "A") (pinfunction "A_A") (pintype "passive"))
      (node (ref "MIN55") (pin "A") (pinfunction "A_A") (pintype "passive"))
      (node (ref "MIN56") (pin "A") (pinfunction "A_A") (pintype "passive"))
      (node (ref "MIN57") (pin "A") (pinfunction "A_A") (pintype "passive"))
      (node (ref "MIN58") (pin "A") (pinfunction "A_A") (pintype "passive"))
      (node (ref "MIN59") (pin "A") (pinfunction "A_A") (pintype "passive"))
      (node (ref "MIN6") (pin "A") (pinfunction "A_A") (pintype "passive"))
      (node (ref "MIN7") (pin "A") (pinfunction "A_A") (pintype "passive"))
      (node (ref "MIN8") (pin "A") (pinfunction "A_A") (pintype "passive"))
      (node (ref "MIN9") (pin "A") (pinfunction "A_A") (pintype "passive"))
      (node (ref "SEC0") (pin "A") (pinfunction "A_A") (pintype "passive"))
      (node (ref "SEC1") (pin "A") (pinfunction "A_A") (pintype "passive"))
      (node (ref "SEC10") (pin "A") (pinfunction "A_A") (pintype "passive"))
      (node (ref "SEC11") (pin "A") (pinfunction "A_A") (pintype "passive"))
      (node (ref "SEC12") (pin "A") (pinfunction "A_A") (pintype "passive"))
      (node (ref "SEC13") (pin "A") (pinfunction "A_A") (pintype "passive"))
      (node (ref "SEC14") (pin "A") (pinfunction "A_A") (pintype "passive"))
      (node (ref "SEC15") (pin "A") (pinfunction "A_A") (pintype "passive"))
      (node (ref "SEC16") (pin "A") (pinfunction "A_A") (pintype "passive"))
      (node (ref "SEC17") (pin "A") (pinfunction "A_A") (pintype "passive"))
      (node (ref "SEC18") (pin "A") (pinfunction "A_A") (pintype "passive"))
      (node (ref "SEC19") (pin "A") (pinfunction "A_A") (pintype "passive"))
      (node (ref "SEC2") (pin "A") (pinfunction "A_A") (pintype "passive"))
      (node (ref "SEC20") (pin "A") (pinfunction "A_A") (pintype "passive"))
      (node (ref "SEC21") (pin "A") (pinfunction "A_A") (pintype "passive"))
      (node (ref "SEC22") (pin "A") (pinfunction "A_A") (pintype "passive"))
      (node (ref "SEC23") (pin "A") (pinfunction "A_A") (pintype "passive"))
      (node (ref "SEC24") (pin "A") (pinfunction "A_A") (pintype "passive"))
      (node (ref "SEC25") (pin "A") (pinfunction "A_A") (pintype "passive"))
      (node (ref "SEC26") (pin "A") (pinfunction "A_A") (pintype "passive"))
      (node (ref "SEC27") (pin "A") (pinfunction "A_A") (pintype "passive"))
      (node (ref "SEC28") (pin "A") (pinfunction "A_A") (pintype "passive"))
      (node (ref "SEC29") (pin "A") (pinfunction "A_A") (pintype "passive"))
      (node (ref "SEC3") (pin "A") (pinfunction "A_A") (pintype "passive"))
      (node (ref "SEC30") (pin "A") (pinfunction "A_A") (pintype "passive"))
      (node (ref "SEC31") (pin "A") (pinfunction "A_A") (pintype "passive"))
      (node (ref "SEC32") (pin "A") (pinfunction "A_A") (pintype "passive"))
      (node (ref "SEC33") (pin "A") (pinfunction "A_A") (pintype "passive"))
      (node (ref "SEC34") (pin "A") (pinfunction "A_A") (pintype "passive"))
      (node (ref "SEC35") (pin "A") (pinfunction "A_A") (pintype "passive"))
      (node (ref "SEC36") (pin "A") (pinfunction "A_A") (pintype "passive"))
      (node (ref "SEC37") (pin "A") (pinfunction "A_A") (pintype "passive"))
      (node (ref "SEC38") (pin "A") (pinfunction "A_A") (pintype "passive"))
      (node (ref "SEC39") (pin "A") (pinfunction "A_A") (pintype "passive"))
      (node (ref "SEC4") (pin "A") (pinfunction "A_A") (pintype "passive"))
      (node (ref "SEC40") (pin "A") (pinfunction "A_A") (pintype "passive"))
      (node (ref "SEC41") (pin "A") (pinfunction "A_A") (pintype "passive"))
      (node (ref "SEC42") (pin "A") (pinfunction "A_A") (pintype "passive"))
      (node (ref "SEC43") (pin "A") (pinfunction "A_A") (pintype "passive"))
      (node (ref "SEC44") (pin "A") (pinfunction "A_A") (pintype "passive"))
      (node (ref "SEC45") (pin "A") (pinfunction "A_A") (pintype "passive"))
      (node (ref "SEC46") (pin "A") (pinfunction "A_A") (pintype "passive"))
      (node (ref "SEC47") (pin "A") (pinfunction "A_A") (pintype "passive"))
      (node (ref "SEC48") (pin "A") (pinfunction "A_A") (pintype "passive"))
      (node (ref "SEC49") (pin "A") (pinfunction "A_A") (pintype "passive"))
      (node (ref "SEC5") (pin "A") (pinfunction "A_A") (pintype "passive"))
      (node (ref "SEC50") (pin "A") (pinfunction "A_A") (pintype "passive"))
      (node (ref "SEC51") (pin "A") (pinfunction "A_A") (pintype "passive"))
      (node (ref "SEC52") (pin "A") (pinfunction "A_A") (pintype "passive"))
      (node (ref "SEC53") (pin "A") (pinfunction "A_A") (pintype "passive"))
      (node (ref "SEC54") (pin "A") (pinfunction "A_A") (pintype "passive"))
      (node (ref "SEC55") (pin "A") (pinfunction "A_A") (pintype "passive"))
      (node (ref "SEC56") (pin "A") (pinfunction "A_A") (pintype "passive"))
      (node (ref "SEC57") (pin "A") (pinfunction "A_A") (pintype "passive"))
      (node (ref "SEC58") (pin "A") (pinfunction "A_A") (pintype "passive"))
      (node (ref "SEC59") (pin "A") (pinfunction "A_A") (pintype "passive"))
      (node (ref "SEC6") (pin "A") (pinfunction "A_A") (pintype "passive"))
      (node (ref "SEC7") (pin "A") (pinfunction "A_A") (pintype "passive"))
      (node (ref "SEC8") (pin "A") (pinfunction "A_A") (pintype "passive"))
      (node (ref "SEC9") (pin "A") (pinfunction "A_A") (pintype "passive"))
    )
    (net (code "2") (name "GND") (class "Default")
      (node (ref "GND") (pin "1") (pinfunction "P$1_1") (pintype "bidirectional"))
      (node (ref "GND46") (pin "1") (pinfunction "P$1_1") (pintype "bidirectional"))
      (node (ref "GND48") (pin "1") (pinfunction "P$1_1") (pintype "bidirectional"))
      (node (ref "ICC1") (pin "4") (pinfunction "GND_4") (pintype "power_in"))
      (node (ref "ICC1") (pin "GND") (pinfunction "GND_GND") (pintype "power_in"))
      (node (ref "ICC2") (pin "4") (pinfunction "GND_4") (pintype "power_in"))
      (node (ref "ICC2") (pin "GND") (pinfunction "GND_GND") (pintype "power_in"))
      (node (ref "ICC3") (pin "4") (pinfunction "GND_4") (pintype "power_in"))
      (node (ref "ICC3") (pin "GND") (pinfunction "GND_GND") (pintype "power_in"))
      (node (ref "ICC4") (pin "4") (pinfunction "GND_4") (pintype "power_in"))
      (node (ref "ICC4") (pin "GND") (pinfunction "GND_GND") (pintype "power_in"))
      (node (ref "ICH1") (pin "4") (pinfunction "GND_4") (pintype "power_in"))
      (node (ref "ICH1") (pin "GND") (pinfunction "GND_GND") (pintype "power_in"))
      (node (ref "ICH10") (pin "4") (pinfunction "GND_4") (pintype "power_in"))
      (node (ref "ICH10") (pin "GND") (pinfunction "GND_GND") (pintype "power_in"))
      (node (ref "ICH13") (pin "4") (pinfunction "GND_4") (pintype "power_in"))
      (node (ref "ICH13") (pin "GND") (pinfunction "GND_GND") (pintype "power_in"))
      (node (ref "ICH14") (pin "4") (pinfunction "GND_4") (pintype "power_in"))
      (node (ref "ICH14") (pin "GND") (pinfunction "GND_GND") (pintype "power_in"))
      (node (ref "ICH17") (pin "4") (pinfunction "GND_4") (pintype "power_in"))
      (node (ref "ICH17") (pin "GND") (pinfunction "GND_GND") (pintype "power_in"))
      (node (ref "ICH18") (pin "4") (pinfunction "GND_4") (pintype "power_in"))
      (node (ref "ICH18") (pin "GND") (pinfunction "GND_GND") (pintype "power_in"))
      (node (ref "ICH2") (pin "4") (pinfunction "GND_4") (pintype "power_in"))
      (node (ref "ICH2") (pin "GND") (pinfunction "GND_GND") (pintype "power_in"))
      (node (ref "ICH21") (pin "4") (pinfunction "GND_4") (pintype "power_in"))
      (node (ref "ICH21") (pin "GND") (pinfunction "GND_GND") (pintype "power_in"))
      (node (ref "ICH22") (pin "4") (pinfunction "GND_4") (pintype "power_in"))
      (node (ref "ICH22") (pin "GND") (pinfunction "GND_GND") (pintype "power_in"))
      (node (ref "ICH25") (pin "4") (pinfunction "GND_4") (pintype "power_in"))
      (node (ref "ICH25") (pin "GND") (pinfunction "GND_GND") (pintype "power_in"))
      (node (ref "ICH26") (pin "4") (pinfunction "GND_4") (pintype "power_in"))
      (node (ref "ICH26") (pin "GND") (pinfunction "GND_GND") (pintype "power_in"))
      (node (ref "ICH29") (pin "4") (pinfunction "GND_4") (pintype "power_in"))
      (node (ref "ICH29") (pin "GND") (pinfunction "GND_GND") (pintype "power_in"))
      (node (ref "ICH30") (pin "4") (pinfunction "GND_4") (pintype "power_in"))
      (node (ref "ICH30") (pin "GND") (pinfunction "GND_GND") (pintype "power_in"))
      (node (ref "ICH33") (pin "4") (pinfunction "GND_4") (pintype "power_in"))
      (node (ref "ICH33") (pin "GND") (pinfunction "GND_GND") (pintype "power_in"))
      (node (ref "ICH34") (pin "4") (pinfunction "GND_4") (pintype "power_in"))
      (node (ref "ICH34") (pin "GND") (pinfunction "GND_GND") (pintype "power_in"))
      (node (ref "ICH37") (pin "4") (pinfunction "GND_4") (pintype "power_in"))
      (node (ref "ICH37") (pin "GND") (pinfunction "GND_GND") (pintype "power_in"))
      (node (ref "ICH41") (pin "4") (pinfunction "GND_4") (pintype "power_in"))
      (node (ref "ICH41") (pin "GND") (pinfunction "GND_GND") (pintype "power_in"))
      (node (ref "ICH5") (pin "4") (pinfunction "GND_4") (pintype "power_in"))
      (node (ref "ICH5") (pin "GND") (pinfunction "GND_GND") (pintype "power_in"))
      (node (ref "ICH6") (pin "4") (pinfunction "GND_4") (pintype "power_in"))
      (node (ref "ICH6") (pin "GND") (pinfunction "GND_GND") (pintype "power_in"))
      (node (ref "ICH9") (pin "4") (pinfunction "GND_4") (pintype "power_in"))
      (node (ref "ICH9") (pin "GND") (pinfunction "GND_GND") (pintype "power_in"))
      (node (ref "ICL11") (pin "4") (pinfunction "GND_4") (pintype "power_in"))
      (node (ref "ICL11") (pin "GND") (pinfunction "GND_GND") (pintype "power_in"))
      (node (ref "ICL12") (pin "4") (pinfunction "GND_4") (pintype "power_in"))
      (node (ref "ICL12") (pin "GND") (pinfunction "GND_GND") (pintype "power_in"))
      (node (ref "ICL15") (pin "4") (pinfunction "GND_4") (pintype "power_in"))
      (node (ref "ICL15") (pin "GND") (pinfunction "GND_GND") (pintype "power_in"))
      (node (ref "ICL16") (pin "4") (pinfunction "GND_4") (pintype "power_in"))
      (node (ref "ICL16") (pin "GND") (pinfunction "GND_GND") (pintype "power_in"))
      (node (ref "ICL19") (pin "4") (pinfunction "GND_4") (pintype "power_in"))
      (node (ref "ICL19") (pin "GND") (pinfunction "GND_GND") (pintype "power_in"))
      (node (ref "ICL20") (pin "4") (pinfunction "GND_4") (pintype "power_in"))
      (node (ref "ICL20") (pin "GND") (pinfunction "GND_GND") (pintype "power_in"))
      (node (ref "ICL23") (pin "4") (pinfunction "GND_4") (pintype "power_in"))
      (node (ref "ICL23") (pin "GND") (pinfunction "GND_GND") (pintype "power_in"))
      (node (ref "ICL24") (pin "4") (pinfunction "GND_4") (pintype "power_in"))
      (node (ref "ICL24") (pin "GND") (pinfunction "GND_GND") (pintype "power_in"))
      (node (ref "ICL27") (pin "4") (pinfunction "GND_4") (pintype "power_in"))
      (node (ref "ICL27") (pin "GND") (pinfunction "GND_GND") (pintype "power_in"))
      (node (ref "ICL28") (pin "4") (pinfunction "GND_4") (pintype "power_in"))
      (node (ref "ICL28") (pin "GND") (pinfunction "GND_GND") (pintype "power_in"))
      (node (ref "ICL3") (pin "4") (pinfunction "GND_4") (pintype "power_in"))
      (node (ref "ICL3") (pin "GND") (pinfunction "GND_GND") (pintype "power_in"))
      (node (ref "ICL31") (pin "4") (pinfunction "GND_4") (pintype "power_in"))
      (node (ref "ICL31") (pin "GND") (pinfunction "GND_GND") (pintype "power_in"))
      (node (ref "ICL32") (pin "4") (pinfunction "GND_4") (pintype "power_in"))
      (node (ref "ICL32") (pin "GND") (pinfunction "GND_GND") (pintype "power_in"))
      (node (ref "ICL35") (pin "4") (pinfunction "GND_4") (pintype "power_in"))
      (node (ref "ICL35") (pin "GND") (pinfunction "GND_GND") (pintype "power_in"))
      (node (ref "ICL36") (pin "4") (pinfunction "GND_4") (pintype "power_in"))
      (node (ref "ICL36") (pin "GND") (pinfunction "GND_GND") (pintype "power_in"))
      (node (ref "ICL39") (pin "4") (pinfunction "GND_4") (pintype "power_in"))
      (node (ref "ICL39") (pin "GND") (pinfunction "GND_GND") (pintype "power_in"))
      (node (ref "ICL4") (pin "4") (pinfunction "GND_4") (pintype "power_in"))
      (node (ref "ICL4") (pin "GND") (pinfunction "GND_GND") (pintype "power_in"))
      (node (ref "ICL43") (pin "4") (pinfunction "GND_4") (pintype "power_in"))
      (node (ref "ICL43") (pin "GND") (pinfunction "GND_GND") (pintype "power_in"))
      (node (ref "ICL7") (pin "4") (pinfunction "GND_4") (pintype "power_in"))
      (node (ref "ICL7") (pin "GND") (pinfunction "GND_GND") (pintype "power_in"))
      (node (ref "ICL8") (pin "4") (pinfunction "GND_4") (pintype "power_in"))
      (node (ref "ICL8") (pin "GND") (pinfunction "GND_GND") (pintype "power_in"))
    )
    (net (code "3") (name "Net-(DIN-P$1)") (class "Default")
      (node (ref "DIN") (pin "1") (pinfunction "P$1_1") (pintype "bidirectional"))
      (node (ref "ICH1") (pin "6") (pinfunction "DIN_6") (pintype "input"))
    )
    (net (code "4") (name "Net-(DOUT-P$1)") (class "Default")
      (node (ref "DOUT") (pin "1") (pinfunction "P$1_1") (pintype "bidirectional"))
      (node (ref "ICC4") (pin "5") (pinfunction "DO_5") (pintype "output"))
    )
    (net (code "5") (name "Net-(ICC1-B)") (class "Default")
      (node (ref "HOUR1") (pin "C") (pinfunction "C_C") (pintype "passive"))
      (node (ref "ICC1") (pin "3") (pinfunction "B_3") (pintype "open_collector"))
    )
    (net (code "6") (name "Net-(ICC1-DIN)") (class "Default")
      (node (ref "ICC1") (pin "6") (pinfunction "DIN_6") (pintype "input"))
      (node (ref "ICL43") (pin "5") (pinfunction "DO_5") (pintype "output"))
    )
    (net (code "7") (name "Net-(ICC1-DO)") (class "Default")
      (node (ref "ICC1") (pin "5") (pinfunction "DO_5") (pintype "output"))
      (node (ref "ICC2") (pin "6") (pinfunction "DIN_6") (pintype "input"))
    )
    (net (code "8") (name "Net-(ICC1-G)") (class "Default")
      (node (ref "HOUR0") (pin "C") (pinfunction "C_C") (pintype "passive"))
      (node (ref "ICC1") (pin "2") (pinfunction "G_2") (pintype "open_collector"))
    )
    (net (code "9") (name "Net-(ICC1-R)") (class "Default")
      (node (ref "HOUR11") (pin "C") (pinfunction "C_C") (pintype "passive"))
      (node (ref "ICC1") (pin "1") (pinfunction "R_1") (pintype "open_collector"))
    )
    (net (code "10") (name "Net-(ICC2-B)") (class "Default")
      (node (ref "HOUR4") (pin "C") (pinfunction "C_C") (pintype "passive"))
      (node (ref "ICC2") (pin "3") (pinfunction "B_3") (pintype "open_collector"))
    )
    (net (code "11") (name "Net-(ICC2-DO)") (class "Default")
      (node (ref "ICC2") (pin "5") (pinfunction "DO_5") (pintype "output"))
      (node (ref "ICC3") (pin "6") (pinfunction "DIN_6") (pintype "input"))
    )
    (net (code "12") (name "Net-(ICC2-G)") (class "Default")
      (node (ref "HOUR3") (pin "C") (pinfunction "C_C") (pintype "passive"))
      (node (ref "ICC2") (pin "2") (pinfunction "G_2") (pintype "open_collector"))
    )
    (net (code "13") (name "Net-(ICC2-R)") (class "Default")
      (node (ref "HOUR2") (pin "C") (pinfunction "C_C") (pintype "passive"))
      (node (ref "ICC2") (pin "1") (pinfunction "R_1") (pintype "open_collector"))
    )
    (net (code "14") (name "Net-(ICC3-B)") (class "Default")
      (node (ref "HOUR7") (pin "C") (pinfunction "C_C") (pintype "passive"))
      (node (ref "ICC3") (pin "3") (pinfunction "B_3") (pintype "open_collector"))
    )
    (net (code "15") (name "Net-(ICC3-DO)") (class "Default")
      (node (ref "ICC3") (pin "5") (pinfunction "DO_5") (pintype "output"))
      (node (ref "ICC4") (pin "6") (pinfunction "DIN_6") (pintype "input"))
    )
    (net (code "16") (name "Net-(ICC3-G)") (class "Default")
      (node (ref "HOUR6") (pin "C") (pinfunction "C_C") (pintype "passive"))
      (node (ref "ICC3") (pin "2") (pinfunction "G_2") (pintype "open_collector"))
    )
    (net (code "17") (name "Net-(ICC3-R)") (class "Default")
      (node (ref "HOUR5") (pin "C") (pinfunction "C_C") (pintype "passive"))
      (node (ref "ICC3") (pin "1") (pinfunction "R_1") (pintype "open_collector"))
    )
    (net (code "18") (name "Net-(ICC4-B)") (class "Default")
      (node (ref "HOUR10") (pin "C") (pinfunction "C_C") (pintype "passive"))
      (node (ref "ICC4") (pin "3") (pinfunction "B_3") (pintype "open_collector"))
    )
    (net (code "19") (name "Net-(ICC4-G)") (class "Default")
      (node (ref "HOUR9") (pin "C") (pinfunction "C_C") (pintype "passive"))
      (node (ref "ICC4") (pin "2") (pinfunction "G_2") (pintype "open_collector"))
    )
    (net (code "20") (name "Net-(ICC4-R)") (class "Default")
      (node (ref "HOUR8") (pin "C") (pinfunction "C_C") (pintype "passive"))
      (node (ref "ICC4") (pin "1") (pinfunction "R_1") (pintype "open_collector"))
    )
    (net (code "21") (name "Net-(ICH1-B)") (class "Default")
      (node (ref "ICH1") (pin "3") (pinfunction "B_3") (pintype "open_collector"))
      (node (ref "SEC1") (pin "C") (pinfunction "C_C") (pintype "passive"))
    )
    (net (code "22") (name "Net-(ICH1-DO)") (class "Default")
      (node (ref "ICH1") (pin "5") (pinfunction "DO_5") (pintype "output"))
      (node (ref "ICH2") (pin "6") (pinfunction "DIN_6") (pintype "input"))
    )
    (net (code "23") (name "Net-(ICH1-G)") (class "Default")
      (node (ref "ICH1") (pin "2") (pinfunction "G_2") (pintype "open_collector"))
      (node (ref "SEC0") (pin "C") (pinfunction "C_C") (pintype "passive"))
    )
    (net (code "24") (name "Net-(ICH1-R)") (class "Default")
      (node (ref "ICH1") (pin "1") (pinfunction "R_1") (pintype "open_collector"))
      (node (ref "SEC59") (pin "C") (pinfunction "C_C") (pintype "passive"))
    )
    (net (code "25") (name "Net-(ICH2-B)") (class "Default")
      (node (ref "ICH2") (pin "3") (pinfunction "B_3") (pintype "open_collector"))
      (node (ref "SEC4") (pin "C") (pinfunction "C_C") (pintype "passive"))
    )
    (net (code "26") (name "Net-(ICH2-DO)") (class "Default")
      (node (ref "ICH2") (pin "5") (pinfunction "DO_5") (pintype "output"))
      (node (ref "ICH5") (pin "6") (pinfunction "DIN_6") (pintype "input"))
    )
    (net (code "27") (name "Net-(ICH2-G)") (class "Default")
      (node (ref "ICH2") (pin "2") (pinfunction "G_2") (pintype "open_collector"))
      (node (ref "SEC3") (pin "C") (pinfunction "C_C") (pintype "passive"))
    )
    (net (code "28") (name "Net-(ICH2-R)") (class "Default")
      (node (ref "ICH2") (pin "1") (pinfunction "R_1") (pintype "open_collector"))
      (node (ref "SEC2") (pin "C") (pinfunction "C_C") (pintype "passive"))
    )
    (net (code "29") (name "Net-(ICH5-B)") (class "Default")
      (node (ref "ICH5") (pin "3") (pinfunction "B_3") (pintype "open_collector"))
      (node (ref "SEC7") (pin "C") (pinfunction "C_C") (pintype "passive"))
    )
    (net (code "30") (name "Net-(ICH5-DO)") (class "Default")
      (node (ref "ICH5") (pin "5") (pinfunction "DO_5") (pintype "output"))
      (node (ref "ICH6") (pin "6") (pinfunction "DIN_6") (pintype "input"))
    )
    (net (code "31") (name "Net-(ICH5-G)") (class "Default")
      (node (ref "ICH5") (pin "2") (pinfunction "G_2") (pintype "open_collector"))
      (node (ref "SEC6") (pin "C") (pinfunction "C_C") (pintype "passive"))
    )
    (net (code "32") (name "Net-(ICH5-R)") (class "Default")
      (node (ref "ICH5") (pin "1") (pinfunction "R_1") (pintype "open_collector"))
      (node (ref "SEC5") (pin "C") (pinfunction "C_C") (pintype "passive"))
    )
    (net (code "33") (name "Net-(ICH6-B)") (class "Default")
      (node (ref "ICH6") (pin "3") (pinfunction "B_3") (pintype "open_collector"))
      (node (ref "SEC10") (pin "C") (pinfunction "C_C") (pintype "passive"))
    )
    (net (code "34") (name "Net-(ICH6-DO)") (class "Default")
      (node (ref "ICH6") (pin "5") (pinfunction "DO_5") (pintype "output"))
      (node (ref "ICH9") (pin "6") (pinfunction "DIN_6") (pintype "input"))
    )
    (net (code "35") (name "Net-(ICH6-G)") (class "Default")
      (node (ref "ICH6") (pin "2") (pinfunction "G_2") (pintype "open_collector"))
      (node (ref "SEC9") (pin "C") (pinfunction "C_C") (pintype "passive"))
    )
    (net (code "36") (name "Net-(ICH6-R)") (class "Default")
      (node (ref "ICH6") (pin "1") (pinfunction "R_1") (pintype "open_collector"))
      (node (ref "SEC8") (pin "C") (pinfunction "C_C") (pintype "passive"))
    )
    (net (code "37") (name "Net-(ICH9-B)") (class "Default")
      (node (ref "ICH9") (pin "3") (pinfunction "B_3") (pintype "open_collector"))
      (node (ref "SEC13") (pin "C") (pinfunction "C_C") (pintype "passive"))
    )
    (net (code "38") (name "Net-(ICH9-G)") (class "Default")
      (node (ref "ICH9") (pin "2") (pinfunction "G_2") (pintype "open_collector"))
      (node (ref "SEC12") (pin "C") (pinfunction "C_C") (pintype "passive"))
    )
    (net (code "39") (name "Net-(ICH9-R)") (class "Default")
      (node (ref "ICH9") (pin "1") (pinfunction "R_1") (pintype "open_collector"))
      (node (ref "SEC11") (pin "C") (pinfunction "C_C") (pintype "passive"))
    )
    (net (code "40") (name "Net-(ICH10-B)") (class "Default")
      (node (ref "ICH10") (pin "3") (pinfunction "B_3") (pintype "open_collector"))
      (node (ref "SEC16") (pin "C") (pinfunction "C_C") (pintype "passive"))
    )
    (net (code "41") (name "Net-(ICH10-DIN)") (class "Default")
      (node (ref "ICH10") (pin "6") (pinfunction "DIN_6") (pintype "input"))
      (node (ref "ICH9") (pin "5") (pinfunction "DO_5") (pintype "output"))
    )
    (net (code "42") (name "Net-(ICH10-DO)") (class "Default")
      (node (ref "ICH10") (pin "5") (pinfunction "DO_5") (pintype "output"))
      (node (ref "ICH13") (pin "6") (pinfunction "DIN_6") (pintype "input"))
    )
    (net (code "43") (name "Net-(ICH10-G)") (class "Default")
      (node (ref "ICH10") (pin "2") (pinfunction "G_2") (pintype "open_collector"))
      (node (ref "SEC15") (pin "C") (pinfunction "C_C") (pintype "passive"))
    )
    (net (code "44") (name "Net-(ICH10-R)") (class "Default")
      (node (ref "ICH10") (pin "1") (pinfunction "R_1") (pintype "open_collector"))
      (node (ref "SEC14") (pin "C") (pinfunction "C_C") (pintype "passive"))
    )
    (net (code "45") (name "Net-(ICH13-B)") (class "Default")
      (node (ref "ICH13") (pin "3") (pinfunction "B_3") (pintype "open_collector"))
      (node (ref "SEC19") (pin "C") (pinfunction "C_C") (pintype "passive"))
    )
    (net (code "46") (name "Net-(ICH13-DO)") (class "Default")
      (node (ref "ICH13") (pin "5") (pinfunction "DO_5") (pintype "output"))
      (node (ref "ICH14") (pin "6") (pinfunction "DIN_6") (pintype "input"))
    )
    (net (code "47") (name "Net-(ICH13-G)") (class "Default")
      (node (ref "ICH13") (pin "2") (pinfunction "G_2") (pintype "open_collector"))
      (node (ref "SEC18") (pin "C") (pinfunction "C_C") (pintype "passive"))
    )
    (net (code "48") (name "Net-(ICH13-R)") (class "Default")
      (node (ref "ICH13") (pin "1") (pinfunction "R_1") (pintype "open_collector"))
      (node (ref "SEC17") (pin "C") (pinfunction "C_C") (pintype "passive"))
    )
    (net (code "49") (name "Net-(ICH14-B)") (class "Default")
      (node (ref "ICH14") (pin "3") (pinfunction "B_3") (pintype "open_collector"))
      (node (ref "SEC22") (pin "C") (pinfunction "C_C") (pintype "passive"))
    )
    (net (code "50") (name "Net-(ICH14-DO)") (class "Default")
      (node (ref "ICH14") (pin "5") (pinfunction "DO_5") (pintype "output"))
      (node (ref "ICH17") (pin "6") (pinfunction "DIN_6") (pintype "input"))
    )
    (net (code "51") (name "Net-(ICH14-G)") (class "Default")
      (node (ref "ICH14") (pin "2") (pinfunction "G_2") (pintype "open_collector"))
      (node (ref "SEC21") (pin "C") (pinfunction "C_C") (pintype "passive"))
    )
    (net (code "52") (name "Net-(ICH14-R)") (class "Default")
      (node (ref "ICH14") (pin "1") (pinfunction "R_1") (pintype "open_collector"))
      (node (ref "SEC20") (pin "C") (pinfunction "C_C") (pintype "passive"))
    )
    (net (code "53") (name "Net-(ICH17-B)") (class "Default")
      (node (ref "ICH17") (pin "3") (pinfunction "B_3") (pintype "open_collector"))
      (node (ref "SEC25") (pin "C") (pinfunction "C_C") (pintype "passive"))
    )
    (net (code "54") (name "Net-(ICH17-DO)") (class "Default")
      (node (ref "ICH17") (pin "5") (pinfunction "DO_5") (pintype "output"))
      (node (ref "ICH18") (pin "6") (pinfunction "DIN_6") (pintype "input"))
    )
    (net (code "55") (name "Net-(ICH17-G)") (class "Default")
      (node (ref "ICH17") (pin "2") (pinfunction "G_2") (pintype "open_collector"))
      (node (ref "SEC24") (pin "C") (pinfunction "C_C") (pintype "passive"))
    )
    (net (code "56") (name "Net-(ICH17-R)") (class "Default")
      (node (ref "ICH17") (pin "1") (pinfunction "R_1") (pintype "open_collector"))
      (node (ref "SEC23") (pin "C") (pinfunction "C_C") (pintype "passive"))
    )
    (net (code "57") (name "Net-(ICH18-B)") (class "Default")
      (node (ref "ICH18") (pin "3") (pinfunction "B_3") (pintype "open_collector"))
      (node (ref "SEC28") (pin "C") (pinfunction "C_C") (pintype "passive"))
    )
    (net (code "58") (name "Net-(ICH18-DO)") (class "Default")
      (node (ref "ICH18") (pin "5") (pinfunction "DO_5") (pintype "output"))
      (node (ref "ICH21") (pin "6") (pinfunction "DIN_6") (pintype "input"))
    )
    (net (code "59") (name "Net-(ICH18-G)") (class "Default")
      (node (ref "ICH18") (pin "2") (pinfunction "G_2") (pintype "open_collector"))
      (node (ref "SEC27") (pin "C") (pinfunction "C_C") (pintype "passive"))
    )
    (net (code "60") (name "Net-(ICH18-R)") (class "Default")
      (node (ref "ICH18") (pin "1") (pinfunction "R_1") (pintype "open_collector"))
      (node (ref "SEC26") (pin "C") (pinfunction "C_C") (pintype "passive"))
    )
    (net (code "61") (name "Net-(ICH21-B)") (class "Default")
      (node (ref "ICH21") (pin "3") (pinfunction "B_3") (pintype "open_collector"))
      (node (ref "SEC31") (pin "C") (pinfunction "C_C") (pintype "passive"))
    )
    (net (code "62") (name "Net-(ICH21-DO)") (class "Default")
      (node (ref "ICH21") (pin "5") (pinfunction "DO_5") (pintype "output"))
      (node (ref "ICH22") (pin "6") (pinfunction "DIN_6") (pintype "input"))
    )
    (net (code "63") (name "Net-(ICH21-G)") (class "Default")
      (node (ref "ICH21") (pin "2") (pinfunction "G_2") (pintype "open_collector"))
      (node (ref "SEC30") (pin "C") (pinfunction "C_C") (pintype "passive"))
    )
    (net (code "64") (name "Net-(ICH21-R)") (class "Default")
      (node (ref "ICH21") (pin "1") (pinfunction "R_1") (pintype "open_collector"))
      (node (ref "SEC29") (pin "C") (pinfunction "C_C") (pintype "passive"))
    )
    (net (code "65") (name "Net-(ICH22-B)") (class "Default")
      (node (ref "ICH22") (pin "3") (pinfunction "B_3") (pintype "open_collector"))
      (node (ref "SEC34") (pin "C") (pinfunction "C_C") (pintype "passive"))
    )
    (net (code "66") (name "Net-(ICH22-DO)") (class "Default")
      (node (ref "ICH22") (pin "5") (pinfunction "DO_5") (pintype "output"))
      (node (ref "ICH25") (pin "6") (pinfunction "DIN_6") (pintype "input"))
    )
    (net (code "67") (name "Net-(ICH22-G)") (class "Default")
      (node (ref "ICH22") (pin "2") (pinfunction "G_2") (pintype "open_collector"))
      (node (ref "SEC33") (pin "C") (pinfunction "C_C") (pintype "passive"))
    )
    (net (code "68") (name "Net-(ICH22-R)") (class "Default")
      (node (ref "ICH22") (pin "1") (pinfunction "R_1") (pintype "open_collector"))
      (node (ref "SEC32") (pin "C") (pinfunction "C_C") (pintype "passive"))
    )
    (net (code "69") (name "Net-(ICH25-B)") (class "Default")
      (node (ref "ICH25") (pin "3") (pinfunction "B_3") (pintype "open_collector"))
      (node (ref "SEC37") (pin "C") (pinfunction "C_C") (pintype "passive"))
    )
    (net (code "70") (name "Net-(ICH25-DO)") (class "Default")
      (node (ref "ICH25") (pin "5") (pinfunction "DO_5") (pintype "output"))
      (node (ref "ICH26") (pin "6") (pinfunction "DIN_6") (pintype "input"))
    )
    (net (code "71") (name "Net-(ICH25-G)") (class "Default")
      (node (ref "ICH25") (pin "2") (pinfunction "G_2") (pintype "open_collector"))
      (node (ref "SEC36") (pin "C") (pinfunction "C_C") (pintype "passive"))
    )
    (net (code "72") (name "Net-(ICH25-R)") (class "Default")
      (node (ref "ICH25") (pin "1") (pinfunction "R_1") (pintype "open_collector"))
      (node (ref "SEC35") (pin "C") (pinfunction "C_C") (pintype "passive"))
    )
    (net (code "73") (name "Net-(ICH26-B)") (class "Default")
      (node (ref "ICH26") (pin "3") (pinfunction "B_3") (pintype "open_collector"))
      (node (ref "SEC40") (pin "C") (pinfunction "C_C") (pintype "passive"))
    )
    (net (code "74") (name "Net-(ICH26-DO)") (class "Default")
      (node (ref "ICH26") (pin "5") (pinfunction "DO_5") (pintype "output"))
      (node (ref "ICH29") (pin "6") (pinfunction "DIN_6") (pintype "input"))
    )
    (net (code "75") (name "Net-(ICH26-G)") (class "Default")
      (node (ref "ICH26") (pin "2") (pinfunction "G_2") (pintype "open_collector"))
      (node (ref "SEC39") (pin "C") (pinfunction "C_C") (pintype "passive"))
    )
    (net (code "76") (name "Net-(ICH26-R)") (class "Default")
      (node (ref "ICH26") (pin "1") (pinfunction "R_1") (pintype "open_collector"))
      (node (ref "SEC38") (pin "C") (pinfunction "C_C") (pintype "passive"))
    )
    (net (code "77") (name "Net-(ICH29-B)") (class "Default")
      (node (ref "ICH29") (pin "3") (pinfunction "B_3") (pintype "open_collector"))
      (node (ref "SEC43") (pin "C") (pinfunction "C_C") (pintype "passive"))
    )
    (net (code "78") (name "Net-(ICH29-DO)") (class "Default")
      (node (ref "ICH29") (pin "5") (pinfunction "DO_5") (pintype "output"))
      (node (ref "ICH30") (pin "6") (pinfunction "DIN_6") (pintype "input"))
    )
    (net (code "79") (name "Net-(ICH29-G)") (class "Default")
      (node (ref "ICH29") (pin "2") (pinfunction "G_2") (pintype "open_collector"))
      (node (ref "SEC42") (pin "C") (pinfunction "C_C") (pintype "passive"))
    )
    (net (code "80") (name "Net-(ICH29-R)") (class "Default")
      (node (ref "ICH29") (pin "1") (pinfunction "R_1") (pintype "open_collector"))
      (node (ref "SEC41") (pin "C") (pinfunction "C_C") (pintype "passive"))
    )
    (net (code "81") (name "Net-(ICH30-B)") (class "Default")
      (node (ref "ICH30") (pin "3") (pinfunction "B_3") (pintype "open_collector"))
      (node (ref "SEC46") (pin "C") (pinfunction "C_C") (pintype "passive"))
    )
    (net (code "82") (name "Net-(ICH30-DO)") (class "Default")
      (node (ref "ICH30") (pin "5") (pinfunction "DO_5") (pintype "output"))
      (node (ref "ICH33") (pin "6") (pinfunction "DIN_6") (pintype "input"))
    )
    (net (code "83") (name "Net-(ICH30-G)") (class "Default")
      (node (ref "ICH30") (pin "2") (pinfunction "G_2") (pintype "open_collector"))
      (node (ref "SEC45") (pin "C") (pinfunction "C_C") (pintype "passive"))
    )
    (net (code "84") (name "Net-(ICH30-R)") (class "Default")
      (node (ref "ICH30") (pin "1") (pinfunction "R_1") (pintype "open_collector"))
      (node (ref "SEC44") (pin "C") (pinfunction "C_C") (pintype "passive"))
    )
    (net (code "85") (name "Net-(ICH33-B)") (class "Default")
      (node (ref "ICH33") (pin "3") (pinfunction "B_3") (pintype "open_collector"))
      (node (ref "SEC49") (pin "C") (pinfunction "C_C") (pintype "passive"))
    )
    (net (code "86") (name "Net-(ICH33-DO)") (class "Default")
      (node (ref "ICH33") (pin "5") (pinfunction "DO_5") (pintype "output"))
      (node (ref "ICH34") (pin "6") (pinfunction "DIN_6") (pintype "input"))
    )
    (net (code "87") (name "Net-(ICH33-G)") (class "Default")
      (node (ref "ICH33") (pin "2") (pinfunction "G_2") (pintype "open_collector"))
      (node (ref "SEC48") (pin "C") (pinfunction "C_C") (pintype "passive"))
    )
    (net (code "88") (name "Net-(ICH33-R)") (class "Default")
      (node (ref "ICH33") (pin "1") (pinfunction "R_1") (pintype "open_collector"))
      (node (ref "SEC47") (pin "C") (pinfunction "C_C") (pintype "passive"))
    )
    (net (code "89") (name "Net-(ICH34-B)") (class "Default")
      (node (ref "ICH34") (pin "3") (pinfunction "B_3") (pintype "open_collector"))
      (node (ref "SEC52") (pin "C") (pinfunction "C_C") (pintype "passive"))
    )
    (net (code "90") (name "Net-(ICH34-DO)") (class "Default")
      (node (ref "ICH34") (pin "5") (pinfunction "DO_5") (pintype "output"))
      (node (ref "ICH37") (pin "6") (pinfunction "DIN_6") (pintype "input"))
    )
    (net (code "91") (name "Net-(ICH34-G)") (class "Default")
      (node (ref "ICH34") (pin "2") (pinfunction "G_2") (pintype "open_collector"))
      (node (ref "SEC51") (pin "C") (pinfunction "C_C") (pintype "passive"))
    )
    (net (code "92") (name "Net-(ICH34-R)") (class "Default")
      (node (ref "ICH34") (pin "1") (pinfunction "R_1") (pintype "open_collector"))
      (node (ref "SEC50") (pin "C") (pinfunction "C_C") (pintype "passive"))
    )
    (net (code "93") (name "Net-(ICH37-B)") (class "Default")
      (node (ref "ICH37") (pin "3") (pinfunction "B_3") (pintype "open_collector"))
      (node (ref "SEC55") (pin "C") (pinfunction "C_C") (pintype "passive"))
    )
    (net (code "94") (name "Net-(ICH37-DO)") (class "Default")
      (node (ref "ICH37") (pin "5") (pinfunction "DO_5") (pintype "output"))
      (node (ref "ICH41") (pin "6") (pinfunction "DIN_6") (pintype "input"))
    )
    (net (code "95") (name "Net-(ICH37-G)") (class "Default")
      (node (ref "ICH37") (pin "2") (pinfunction "G_2") (pintype "open_collector"))
      (node (ref "SEC54") (pin "C") (pinfunction "C_C") (pintype "passive"))
    )
    (net (code "96") (name "Net-(ICH37-R)") (class "Default")
      (node (ref "ICH37") (pin "1") (pinfunction "R_1") (pintype "open_collector"))
      (node (ref "SEC53") (pin "C") (pinfunction "C_C") (pintype "passive"))
    )
    (net (code "97") (name "Net-(ICH41-B)") (class "Default")
      (node (ref "ICH41") (pin "3") (pinfunction "B_3") (pintype "open_collector"))
      (node (ref "SEC58") (pin "C") (pinfunction "C_C") (pintype "passive"))
    )
    (net (code "98") (name "Net-(ICH41-DO)") (class "Default")
      (node (ref "ICH41") (pin "5") (pinfunction "DO_5") (pintype "output"))
      (node (ref "ICL3") (pin "6") (pinfunction "DIN_6") (pintype "input"))
    )
    (net (code "99") (name "Net-(ICH41-G)") (class "Default")
      (node (ref "ICH41") (pin "2") (pinfunction "G_2") (pintype "open_collector"))
      (node (ref "SEC57") (pin "C") (pinfunction "C_C") (pintype "passive"))
    )
    (net (code "100") (name "Net-(ICH41-R)") (class "Default")
      (node (ref "ICH41") (pin "1") (pinfunction "R_1") (pintype "open_collector"))
      (node (ref "SEC56") (pin "C") (pinfunction "C_C") (pintype "passive"))
    )
    (net (code "101") (name "Net-(ICL3-B)") (class "Default")
      (node (ref "ICL3") (pin "3") (pinfunction "B_3") (pintype "open_collector"))
      (node (ref "MIN1") (pin "C") (pinfunction "C_C") (pintype "passive"))
    )
    (net (code "102") (name "Net-(ICL3-DO)") (class "Default")
      (node (ref "ICL3") (pin "5") (pinfunction "DO_5") (pintype "output"))
      (node (ref "ICL4") (pin "6") (pinfunction "DIN_6") (pintype "input"))
    )
    (net (code "103") (name "Net-(ICL3-G)") (class "Default")
      (node (ref "ICL3") (pin "2") (pinfunction "G_2") (pintype "open_collector"))
      (node (ref "MIN0") (pin "C") (pinfunction "C_C") (pintype "passive"))
    )
    (net (code "104") (name "Net-(ICL3-R)") (class "Default")
      (node (ref "ICL3") (pin "1") (pinfunction "R_1") (pintype "open_collector"))
      (node (ref "MIN59") (pin "C") (pinfunction "C_C") (pintype "passive"))
    )
    (net (code "105") (name "Net-(ICL4-B)") (class "Default")
      (node (ref "ICL4") (pin "3") (pinfunction "B_3") (pintype "open_collector"))
      (node (ref "MIN4") (pin "C") (pinfunction "C_C") (pintype "passive"))
    )
    (net (code "106") (name "Net-(ICL4-DO)") (class "Default")
      (node (ref "ICL4") (pin "5") (pinfunction "DO_5") (pintype "output"))
      (node (ref "ICL7") (pin "6") (pinfunction "DIN_6") (pintype "input"))
    )
    (net (code "107") (name "Net-(ICL4-G)") (class "Default")
      (node (ref "ICL4") (pin "2") (pinfunction "G_2") (pintype "open_collector"))
      (node (ref "MIN3") (pin "C") (pinfunction "C_C") (pintype "passive"))
    )
    (net (code "108") (name "Net-(ICL4-R)") (class "Default")
      (node (ref "ICL4") (pin "1") (pinfunction "R_1") (pintype "open_collector"))
      (node (ref "MIN2") (pin "C") (pinfunction "C_C") (pintype "passive"))
    )
    (net (code "109") (name "Net-(ICL7-B)") (class "Default")
      (node (ref "ICL7") (pin "3") (pinfunction "B_3") (pintype "open_collector"))
      (node (ref "MIN7") (pin "C") (pinfunction "C_C") (pintype "passive"))
    )
    (net (code "110") (name "Net-(ICL7-DO)") (class "Default")
      (node (ref "ICL7") (pin "5") (pinfunction "DO_5") (pintype "output"))
      (node (ref "ICL8") (pin "6") (pinfunction "DIN_6") (pintype "input"))
    )
    (net (code "111") (name "Net-(ICL7-G)") (class "Default")
      (node (ref "ICL7") (pin "2") (pinfunction "G_2") (pintype "open_collector"))
      (node (ref "MIN6") (pin "C") (pinfunction "C_C") (pintype "passive"))
    )
    (net (code "112") (name "Net-(ICL7-R)") (class "Default")
      (node (ref "ICL7") (pin "1") (pinfunction "R_1") (pintype "open_collector"))
      (node (ref "MIN5") (pin "C") (pinfunction "C_C") (pintype "passive"))
    )
    (net (code "113") (name "Net-(ICL8-B)") (class "Default")
      (node (ref "ICL8") (pin "3") (pinfunction "B_3") (pintype "open_collector"))
      (node (ref "MIN10") (pin "C") (pinfunction "C_C") (pintype "passive"))
    )
    (net (code "114") (name "Net-(ICL8-G)") (class "Default")
      (node (ref "ICL8") (pin "2") (pinfunction "G_2") (pintype "open_collector"))
      (node (ref "MIN9") (pin "C") (pinfunction "C_C") (pintype "passive"))
    )
    (net (code "115") (name "Net-(ICL8-R)") (class "Default")
      (node (ref "ICL8") (pin "1") (pinfunction "R_1") (pintype "open_collector"))
      (node (ref "MIN8") (pin "C") (pinfunction "C_C") (pintype "passive"))
    )
    (net (code "116") (name "Net-(ICL11-B)") (class "Default")
      (node (ref "ICL11") (pin "3") (pinfunction "B_3") (pintype "open_collector"))
      (node (ref "MIN13") (pin "C") (pinfunction "C_C") (pintype "passive"))
    )
    (net (code "117") (name "Net-(ICL11-DIN)") (class "Default")
      (node (ref "ICL11") (pin "6") (pinfunction "DIN_6") (pintype "input"))
      (node (ref "ICL8") (pin "5") (pinfunction "DO_5") (pintype "output"))
    )
    (net (code "118") (name "Net-(ICL11-DO)") (class "Default")
      (node (ref "ICL11") (pin "5") (pinfunction "DO_5") (pintype "output"))
      (node (ref "ICL12") (pin "6") (pinfunction "DIN_6") (pintype "input"))
    )
    (net (code "119") (name "Net-(ICL11-G)") (class "Default")
      (node (ref "ICL11") (pin "2") (pinfunction "G_2") (pintype "open_collector"))
      (node (ref "MIN12") (pin "C") (pinfunction "C_C") (pintype "passive"))
    )
    (net (code "120") (name "Net-(ICL11-R)") (class "Default")
      (node (ref "ICL11") (pin "1") (pinfunction "R_1") (pintype "open_collector"))
      (node (ref "MIN11") (pin "C") (pinfunction "C_C") (pintype "passive"))
    )
    (net (code "121") (name "Net-(ICL12-B)") (class "Default")
      (node (ref "ICL12") (pin "3") (pinfunction "B_3") (pintype "open_collector"))
      (node (ref "MIN16") (pin "C") (pinfunction "C_C") (pintype "passive"))
    )
    (net (code "122") (name "Net-(ICL12-DO)") (class "Default")
      (node (ref "ICL12") (pin "5") (pinfunction "DO_5") (pintype "output"))
      (node (ref "ICL15") (pin "6") (pinfunction "DIN_6") (pintype "input"))
    )
    (net (code "123") (name "Net-(ICL12-G)") (class "Default")
      (node (ref "ICL12") (pin "2") (pinfunction "G_2") (pintype "open_collector"))
      (node (ref "MIN15") (pin "C") (pinfunction "C_C") (pintype "passive"))
    )
    (net (code "124") (name "Net-(ICL12-R)") (class "Default")
      (node (ref "ICL12") (pin "1") (pinfunction "R_1") (pintype "open_collector"))
      (node (ref "MIN14") (pin "C") (pinfunction "C_C") (pintype "passive"))
    )
    (net (code "125") (name "Net-(ICL15-B)") (class "Default")
      (node (ref "ICL15") (pin "3") (pinfunction "B_3") (pintype "open_collector"))
      (node (ref "MIN19") (pin "C") (pinfunction "C_C") (pintype "passive"))
    )
    (net (code "126") (name "Net-(ICL15-DO)") (class "Default")
      (node (ref "ICL15") (pin "5") (pinfunction "DO_5") (pintype "output"))
      (node (ref "ICL16") (pin "6") (pinfunction "DIN_6") (pintype "input"))
    )
    (net (code "127") (name "Net-(ICL15-G)") (class "Default")
      (node (ref "ICL15") (pin "2") (pinfunction "G_2") (pintype "open_collector"))
      (node (ref "MIN18") (pin "C") (pinfunction "C_C") (pintype "passive"))
    )
    (net (code "128") (name "Net-(ICL15-R)") (class "Default")
      (node (ref "ICL15") (pin "1") (pinfunction "R_1") (pintype "open_collector"))
      (node (ref "MIN17") (pin "C") (pinfunction "C_C") (pintype "passive"))
    )
    (net (code "129") (name "Net-(ICL16-B)") (class "Default")
      (node (ref "ICL16") (pin "3") (pinfunction "B_3") (pintype "open_collector"))
      (node (ref "MIN22") (pin "C") (pinfunction "C_C") (pintype "passive"))
    )
    (net (code "130") (name "Net-(ICL16-DO)") (class "Default")
      (node (ref "ICL16") (pin "5") (pinfunction "DO_5") (pintype "output"))
      (node (ref "ICL19") (pin "6") (pinfunction "DIN_6") (pintype "input"))
    )
    (net (code "131") (name "Net-(ICL16-G)") (class "Default")
      (node (ref "ICL16") (pin "2") (pinfunction "G_2") (pintype "open_collector"))
      (node (ref "MIN21") (pin "C") (pinfunction "C_C") (pintype "passive"))
    )
    (net (code "132") (name "Net-(ICL16-R)") (class "Default")
      (node (ref "ICL16") (pin "1") (pinfunction "R_1") (pintype "open_collector"))
      (node (ref "MIN20") (pin "C") (pinfunction "C_C") (pintype "passive"))
    )
    (net (code "133") (name "Net-(ICL19-B)") (class "Default")
      (node (ref "ICL19") (pin "3") (pinfunction "B_3") (pintype "open_collector"))
      (node (ref "MIN25") (pin "C") (pinfunction "C_C") (pintype "passive"))
    )
    (net (code "134") (name "Net-(ICL19-DO)") (class "Default")
      (node (ref "ICL19") (pin "5") (pinfunction "DO_5") (pintype "output"))
      (node (ref "ICL20") (pin "6") (pinfunction "DIN_6") (pintype "input"))
    )
    (net (code "135") (name "Net-(ICL19-G)") (class "Default")
      (node (ref "ICL19") (pin "2") (pinfunction "G_2") (pintype "open_collector"))
      (node (ref "MIN24") (pin "C") (pinfunction "C_C") (pintype "passive"))
    )
    (net (code "136") (name "Net-(ICL19-R)") (class "Default")
      (node (ref "ICL19") (pin "1") (pinfunction "R_1") (pintype "open_collector"))
      (node (ref "MIN23") (pin "C") (pinfunction "C_C") (pintype "passive"))
    )
    (net (code "137") (name "Net-(ICL20-B)") (class "Default")
      (node (ref "ICL20") (pin "3") (pinfunction "B_3") (pintype "open_collector"))
      (node (ref "MIN28") (pin "C") (pinfunction "C_C") (pintype "passive"))
    )
    (net (code "138") (name "Net-(ICL20-DO)") (class "Default")
      (node (ref "ICL20") (pin "5") (pinfunction "DO_5") (pintype "output"))
      (node (ref "ICL23") (pin "6") (pinfunction "DIN_6") (pintype "input"))
    )
    (net (code "139") (name "Net-(ICL20-G)") (class "Default")
      (node (ref "ICL20") (pin "2") (pinfunction "G_2") (pintype "open_collector"))
      (node (ref "MIN27") (pin "C") (pinfunction "C_C") (pintype "passive"))
    )
    (net (code "140") (name "Net-(ICL20-R)") (class "Default")
      (node (ref "ICL20") (pin "1") (pinfunction "R_1") (pintype "open_collector"))
      (node (ref "MIN26") (pin "C") (pinfunction "C_C") (pintype "passive"))
    )
    (net (code "141") (name "Net-(ICL23-B)") (class "Default")
      (node (ref "ICL23") (pin "3") (pinfunction "B_3") (pintype "open_collector"))
      (node (ref "MIN31") (pin "C") (pinfunction "C_C") (pintype "passive"))
    )
    (net (code "142") (name "Net-(ICL23-DO)") (class "Default")
      (node (ref "ICL23") (pin "5") (pinfunction "DO_5") (pintype "output"))
      (node (ref "ICL24") (pin "6") (pinfunction "DIN_6") (pintype "input"))
    )
    (net (code "143") (name "Net-(ICL23-G)") (class "Default")
      (node (ref "ICL23") (pin "2") (pinfunction "G_2") (pintype "open_collector"))
      (node (ref "MIN30") (pin "C") (pinfunction "C_C") (pintype "passive"))
    )
    (net (code "144") (name "Net-(ICL23-R)") (class "Default")
      (node (ref "ICL23") (pin "1") (pinfunction "R_1") (pintype "open_collector"))
      (node (ref "MIN29") (pin "C") (pinfunction "C_C") (pintype "passive"))
    )
    (net (code "145") (name "Net-(ICL24-B)") (class "Default")
      (node (ref "ICL24") (pin "3") (pinfunction "B_3") (pintype "open_collector"))
      (node (ref "MIN34") (pin "C") (pinfunction "C_C") (pintype "passive"))
    )
    (net (code "146") (name "Net-(ICL24-DO)") (class "Default")
      (node (ref "ICL24") (pin "5") (pinfunction "DO_5") (pintype "output"))
      (node (ref "ICL27") (pin "6") (pinfunction "DIN_6") (pintype "input"))
    )
    (net (code "147") (name "Net-(ICL24-G)") (class "Default")
      (node (ref "ICL24") (pin "2") (pinfunction "G_2") (pintype "open_collector"))
      (node (ref "MIN33") (pin "C") (pinfunction "C_C") (pintype "passive"))
    )
    (net (code "148") (name "Net-(ICL24-R)") (class "Default")
      (node (ref "ICL24") (pin "1") (pinfunction "R_1") (pintype "open_collector"))
      (node (ref "MIN32") (pin "C") (pinfunction "C_C") (pintype "passive"))
    )
    (net (code "149") (name "Net-(ICL27-B)") (class "Default")
      (node (ref "ICL27") (pin "3") (pinfunction "B_3") (pintype "open_collector"))
      (node (ref "MIN37") (pin "C") (pinfunction "C_C") (pintype "passive"))
    )
    (net (code "150") (name "Net-(ICL27-DO)") (class "Default")
      (node (ref "ICL27") (pin "5") (pinfunction "DO_5") (pintype "output"))
      (node (ref "ICL28") (pin "6") (pinfunction "DIN_6") (pintype "input"))
    )
    (net (code "151") (name "Net-(ICL27-G)") (class "Default")
      (node (ref "ICL27") (pin "2") (pinfunction "G_2") (pintype "open_collector"))
      (node (ref "MIN36") (pin "C") (pinfunction "C_C") (pintype "passive"))
    )
    (net (code "152") (name "Net-(ICL27-R)") (class "Default")
      (node (ref "ICL27") (pin "1") (pinfunction "R_1") (pintype "open_collector"))
      (node (ref "MIN35") (pin "C") (pinfunction "C_C") (pintype "passive"))
    )
    (net (code "153") (name "Net-(ICL28-B)") (class "Default")
      (node (ref "ICL28") (pin "3") (pinfunction "B_3") (pintype "open_collector"))
      (node (ref "MIN40") (pin "C") (pinfunction "C_C") (pintype "passive"))
    )
    (net (code "154") (name "Net-(ICL28-DO)") (class "Default")
      (node (ref "ICL28") (pin "5") (pinfunction "DO_5") (pintype "output"))
      (node (ref "ICL31") (pin "6") (pinfunction "DIN_6") (pintype "input"))
    )
    (net (code "155") (name "Net-(ICL28-G)") (class "Default")
      (node (ref "ICL28") (pin "2") (pinfunction "G_2") (pintype "open_collector"))
      (node (ref "MIN39") (pin "C") (pinfunction "C_C") (pintype "passive"))
    )
    (net (code "156") (name "Net-(ICL28-R)") (class "Default")
      (node (ref "ICL28") (pin "1") (pinfunction "R_1") (pintype "open_collector"))
      (node (ref "MIN38") (pin "C") (pinfunction "C_C") (pintype "passive"))
    )
    (net (code "157") (name "Net-(ICL31-B)") (class "Default")
      (node (ref "ICL31") (pin "3") (pinfunction "B_3") (pintype "open_collector"))
      (node (ref "MIN43") (pin "C") (pinfunction "C_C") (pintype "passive"))
    )
    (net (code "158") (name "Net-(ICL31-DO)") (class "Default")
      (node (ref "ICL31") (pin "5") (pinfunction "DO_5") (pintype "output"))
      (node (ref "ICL32") (pin "6") (pinfunction "DIN_6") (pintype "input"))
    )
    (net (code "159") (name "Net-(ICL31-G)") (class "Default")
      (node (ref "ICL31") (pin "2") (pinfunction "G_2") (pintype "open_collector"))
      (node (ref "MIN42") (pin "C") (pinfunction "C_C") (pintype "passive"))
    )
    (net (code "160") (name "Net-(ICL31-R)") (class "Default")
      (node (ref "ICL31") (pin "1") (pinfunction "R_1") (pintype "open_collector"))
      (node (ref "MIN41") (pin "C") (pinfunction "C_C") (pintype "passive"))
    )
    (net (code "161") (name "Net-(ICL32-B)") (class "Default")
      (node (ref "ICL32") (pin "3") (pinfunction "B_3") (pintype "open_collector"))
      (node (ref "MIN46") (pin "C") (pinfunction "C_C") (pintype "passive"))
    )
    (net (code "162") (name "Net-(ICL32-DO)") (class "Default")
      (node (ref "ICL32") (pin "5") (pinfunction "DO_5") (pintype "output"))
      (node (ref "ICL35") (pin "6") (pinfunction "DIN_6") (pintype "input"))
    )
    (net (code "163") (name "Net-(ICL32-G)") (class "Default")
      (node (ref "ICL32") (pin "2") (pinfunction "G_2") (pintype "open_collector"))
      (node (ref "MIN45") (pin "C") (pinfunction "C_C") (pintype "passive"))
    )
    (net (code "164") (name "Net-(ICL32-R)") (class "Default")
      (node (ref "ICL32") (pin "1") (pinfunction "R_1") (pintype "open_collector"))
      (node (ref "MIN44") (pin "C") (pinfunction "C_C") (pintype "passive"))
    )
    (net (code "165") (name "Net-(ICL35-B)") (class "Default")
      (node (ref "ICL35") (pin "3") (pinfunction "B_3") (pintype "open_collector"))
      (node (ref "MIN49") (pin "C") (pinfunction "C_C") (pintype "passive"))
    )
    (net (code "166") (name "Net-(ICL35-DO)") (class "Default")
      (node (ref "ICL35") (pin "5") (pinfunction "DO_5") (pintype "output"))
      (node (ref "ICL36") (pin "6") (pinfunction "DIN_6") (pintype "input"))
    )
    (net (code "167") (name "Net-(ICL35-G)") (class "Default")
      (node (ref "ICL35") (pin "2") (pinfunction "G_2") (pintype "open_collector"))
      (node (ref "MIN48") (pin "C") (pinfunction "C_C") (pintype "passive"))
    )
    (net (code "168") (name "Net-(ICL35-R)") (class "Default")
      (node (ref "ICL35") (pin "1") (pinfunction "R_1") (pintype "open_collector"))
      (node (ref "MIN47") (pin "C") (pinfunction "C_C") (pintype "passive"))
    )
    (net (code "169") (name "Net-(ICL36-B)") (class "Default")
      (node (ref "ICL36") (pin "3") (pinfunction "B_3") (pintype "open_collector"))
      (node (ref "MIN52") (pin "C") (pinfunction "C_C") (pintype "passive"))
    )
    (net (code "170") (name "Net-(ICL36-DO)") (class "Default")
      (node (ref "ICL36") (pin "5") (pinfunction "DO_5") (pintype "output"))
      (node (ref "ICL39") (pin "6") (pinfunction "DIN_6") (pintype "input"))
    )
    (net (code "171") (name "Net-(ICL36-G)") (class "Default")
      (node (ref "ICL36") (pin "2") (pinfunction "G_2") (pintype "open_collector"))
      (node (ref "MIN51") (pin "C") (pinfunction "C_C") (pintype "passive"))
    )
    (net (code "172") (name "Net-(ICL36-R)") (class "Default")
      (node (ref "ICL36") (pin "1") (pinfunction "R_1") (pintype "open_collector"))
      (node (ref "MIN50") (pin "C") (pinfunction "C_C") (pintype "passive"))
    )
    (net (code "173") (name "Net-(ICL39-B)") (class "Default")
      (node (ref "ICL39") (pin "3") (pinfunction "B_3") (pintype "open_collector"))
      (node (ref "MIN55") (pin "C") (pinfunction "C_C") (pintype "passive"))
    )
    (net (code "174") (name "Net-(ICL39-DO)") (class "Default")
      (node (ref "ICL39") (pin "5") (pinfunction "DO_5") (pintype "output"))
      (node (ref "ICL43") (pin "6") (pinfunction "DIN_6") (pintype "input"))
    )
    (net (code "175") (name "Net-(ICL39-G)") (class "Default")
      (node (ref "ICL39") (pin "2") (pinfunction "G_2") (pintype "open_collector"))
      (node (ref "MIN54") (pin "C") (pinfunction "C_C") (pintype "passive"))
    )
    (net (code "176") (name "Net-(ICL39-R)") (class "Default")
      (node (ref "ICL39") (pin "1") (pinfunction "R_1") (pintype "open_collector"))
      (node (ref "MIN53") (pin "C") (pinfunction "C_C") (pintype "passive"))
    )
    (net (code "177") (name "Net-(ICL43-B)") (class "Default")
      (node (ref "ICL43") (pin "3") (pinfunction "B_3") (pintype "open_collector"))
      (node (ref "MIN58") (pin "C") (pinfunction "C_C") (pintype "passive"))
    )
    (net (code "178") (name "Net-(ICL43-G)") (class "Default")
      (node (ref "ICL43") (pin "2") (pinfunction "G_2") (pintype "open_collector"))
      (node (ref "MIN57") (pin "C") (pinfunction "C_C") (pintype "passive"))
    )
    (net (code "179") (name "Net-(ICL43-R)") (class "Default")
      (node (ref "ICL43") (pin "1") (pinfunction "R_1") (pintype "open_collector"))
      (node (ref "MIN56") (pin "C") (pinfunction "C_C") (pintype "passive"))
    )
    (net (code "180") (name "Net-(TOUCH-P$1)") (class "Default")
      (node (ref "TOUCH") (pin "1") (pinfunction "P$1_1") (pintype "bidirectional"))
      (node (ref "U$2") (pin "P$1") (pinfunction "P$1_P$1") (pintype "bidirectional"))
      (node (ref "U$2") (pin "P$2") (pinfunction "P$1_P$2") (pintype "bidirectional"))
    )
    (net (code "181") (name "unconnected-(ICC1-SET-Pad7)") (class "Default")
      (node (ref "ICC1") (pin "7") (pinfunction "SET_7") (pintype "input"))
    )
    (net (code "182") (name "unconnected-(ICC2-SET-Pad7)") (class "Default")
      (node (ref "ICC2") (pin "7") (pinfunction "SET_7") (pintype "input"))
    )
    (net (code "183") (name "unconnected-(ICC3-SET-Pad7)") (class "Default")
      (node (ref "ICC3") (pin "7") (pinfunction "SET_7") (pintype "input"))
    )
    (net (code "184") (name "unconnected-(ICC4-SET-Pad7)") (class "Default")
      (node (ref "ICC4") (pin "7") (pinfunction "SET_7") (pintype "input"))
    )
    (net (code "185") (name "unconnected-(ICH1-SET-Pad7)") (class "Default")
      (node (ref "ICH1") (pin "7") (pinfunction "SET_7") (pintype "input"))
    )
    (net (code "186") (name "unconnected-(ICH2-SET-Pad7)") (class "Default")
      (node (ref "ICH2") (pin "7") (pinfunction "SET_7") (pintype "input"))
    )
    (net (code "187") (name "unconnected-(ICH5-SET-Pad7)") (class "Default")
      (node (ref "ICH5") (pin "7") (pinfunction "SET_7") (pintype "input"))
    )
    (net (code "188") (name "unconnected-(ICH6-SET-Pad7)") (class "Default")
      (node (ref "ICH6") (pin "7") (pinfunction "SET_7") (pintype "input"))
    )
    (net (code "189") (name "unconnected-(ICH9-SET-Pad7)") (class "Default")
      (node (ref "ICH9") (pin "7") (pinfunction "SET_7") (pintype "input"))
    )
    (net (code "190") (name "unconnected-(ICH10-SET-Pad7)") (class "Default")
      (node (ref "ICH10") (pin "7") (pinfunction "SET_7") (pintype "input"))
    )
    (net (code "191") (name "unconnected-(ICH13-SET-Pad7)") (class "Default")
      (node (ref "ICH13") (pin "7") (pinfunction "SET_7") (pintype "input"))
    )
    (net (code "192") (name "unconnected-(ICH14-SET-Pad7)") (class "Default")
      (node (ref "ICH14") (pin "7") (pinfunction "SET_7") (pintype "input"))
    )
    (net (code "193") (name "unconnected-(ICH17-SET-Pad7)") (class "Default")
      (node (ref "ICH17") (pin "7") (pinfunction "SET_7") (pintype "input"))
    )
    (net (code "194") (name "unconnected-(ICH18-SET-Pad7)") (class "Default")
      (node (ref "ICH18") (pin "7") (pinfunction "SET_7") (pintype "input"))
    )
    (net (code "195") (name "unconnected-(ICH21-SET-Pad7)") (class "Default")
      (node (ref "ICH21") (pin "7") (pinfunction "SET_7") (pintype "input"))
    )
    (net (code "196") (name "unconnected-(ICH22-SET-Pad7)") (class "Default")
      (node (ref "ICH22") (pin "7") (pinfunction "SET_7") (pintype "input"))
    )
    (net (code "197") (name "unconnected-(ICH25-SET-Pad7)") (class "Default")
      (node (ref "ICH25") (pin "7") (pinfunction "SET_7") (pintype "input"))
    )
    (net (code "198") (name "unconnected-(ICH26-SET-Pad7)") (class "Default")
      (node (ref "ICH26") (pin "7") (pinfunction "SET_7") (pintype "input"))
    )
    (net (code "199") (name "unconnected-(ICH29-SET-Pad7)") (class "Default")
      (node (ref "ICH29") (pin "7") (pinfunction "SET_7") (pintype "input"))
    )
    (net (code "200") (name "unconnected-(ICH30-SET-Pad7)") (class "Default")
      (node (ref "ICH30") (pin "7") (pinfunction "SET_7") (pintype "input"))
    )
    (net (code "201") (name "unconnected-(ICH33-SET-Pad7)") (class "Default")
      (node (ref "ICH33") (pin "7") (pinfunction "SET_7") (pintype "input"))
    )
    (net (code "202") (name "unconnected-(ICH34-SET-Pad7)") (class "Default")
      (node (ref "ICH34") (pin "7") (pinfunction "SET_7") (pintype "input"))
    )
    (net (code "203") (name "unconnected-(ICH37-SET-Pad7)") (class "Default")
      (node (ref "ICH37") (pin "7") (pinfunction "SET_7") (pintype "input"))
    )
    (net (code "204") (name "unconnected-(ICH41-SET-Pad7)") (class "Default")
      (node (ref "ICH41") (pin "7") (pinfunction "SET_7") (pintype "input"))
    )
    (net (code "205") (name "unconnected-(ICL3-SET-Pad7)") (class "Default")
      (node (ref "ICL3") (pin "7") (pinfunction "SET_7") (pintype "input"))
    )
    (net (code "206") (name "unconnected-(ICL4-SET-Pad7)") (class "Default")
      (node (ref "ICL4") (pin "7") (pinfunction "SET_7") (pintype "input"))
    )
    (net (code "207") (name "unconnected-(ICL7-SET-Pad7)") (class "Default")
      (node (ref "ICL7") (pin "7") (pinfunction "SET_7") (pintype "input"))
    )
    (net (code "208") (name "unconnected-(ICL8-SET-Pad7)") (class "Default")
      (node (ref "ICL8") (pin "7") (pinfunction "SET_7") (pintype "input"))
    )
    (net (code "209") (name "unconnected-(ICL11-SET-Pad7)") (class "Default")
      (node (ref "ICL11") (pin "7") (pinfunction "SET_7") (pintype "input"))
    )
    (net (code "210") (name "unconnected-(ICL12-SET-Pad7)") (class "Default")
      (node (ref "ICL12") (pin "7") (pinfunction "SET_7") (pintype "input"))
    )
    (net (code "211") (name "unconnected-(ICL15-SET-Pad7)") (class "Default")
      (node (ref "ICL15") (pin "7") (pinfunction "SET_7") (pintype "input"))
    )
    (net (code "212") (name "unconnected-(ICL16-SET-Pad7)") (class "Default")
      (node (ref "ICL16") (pin "7") (pinfunction "SET_7") (pintype "input"))
    )
    (net (code "213") (name "unconnected-(ICL19-SET-Pad7)") (class "Default")
      (node (ref "ICL19") (pin "7") (pinfunction "SET_7") (pintype "input"))
    )
    (net (code "214") (name "unconnected-(ICL20-SET-Pad7)") (class "Default")
      (node (ref "ICL20") (pin "7") (pinfunction "SET_7") (pintype "input"))
    )
    (net (code "215") (name "unconnected-(ICL23-SET-Pad7)") (class "Default")
      (node (ref "ICL23") (pin "7") (pinfunction "SET_7") (pintype "input"))
    )
    (net (code "216") (name "unconnected-(ICL24-SET-Pad7)") (class "Default")
      (node (ref "ICL24") (pin "7") (pinfunction "SET_7") (pintype "input"))
    )
    (net (code "217") (name "unconnected-(ICL27-SET-Pad7)") (class "Default")
      (node (ref "ICL27") (pin "7") (pinfunction "SET_7") (pintype "input"))
    )
    (net (code "218") (name "unconnected-(ICL28-SET-Pad7)") (class "Default")
      (node (ref "ICL28") (pin "7") (pinfunction "SET_7") (pintype "input"))
    )
    (net (code "219") (name "unconnected-(ICL31-SET-Pad7)") (class "Default")
      (node (ref "ICL31") (pin "7") (pinfunction "SET_7") (pintype "input"))
    )
    (net (code "220") (name "unconnected-(ICL32-SET-Pad7)") (class "Default")
      (node (ref "ICL32") (pin "7") (pinfunction "SET_7") (pintype "input"))
    )
    (net (code "221") (name "unconnected-(ICL35-SET-Pad7)") (class "Default")
      (node (ref "ICL35") (pin "7") (pinfunction "SET_7") (pintype "input"))
    )
    (net (code "222") (name "unconnected-(ICL36-SET-Pad7)") (class "Default")
      (node (ref "ICL36") (pin "7") (pinfunction "SET_7") (pintype "input"))
    )
    (net (code "223") (name "unconnected-(ICL39-SET-Pad7)") (class "Default")
      (node (ref "ICL39") (pin "7") (pinfunction "SET_7") (pintype "input"))
    )
    (net (code "224") (name "unconnected-(ICL43-SET-Pad7)") (class "Default")
      (node (ref "ICL43") (pin "7") (pinfunction "SET_7") (pintype "input"))
    )
  )
)
